# alarm_controller.net
KiCad netlist of a schematic drawn in EAGLE
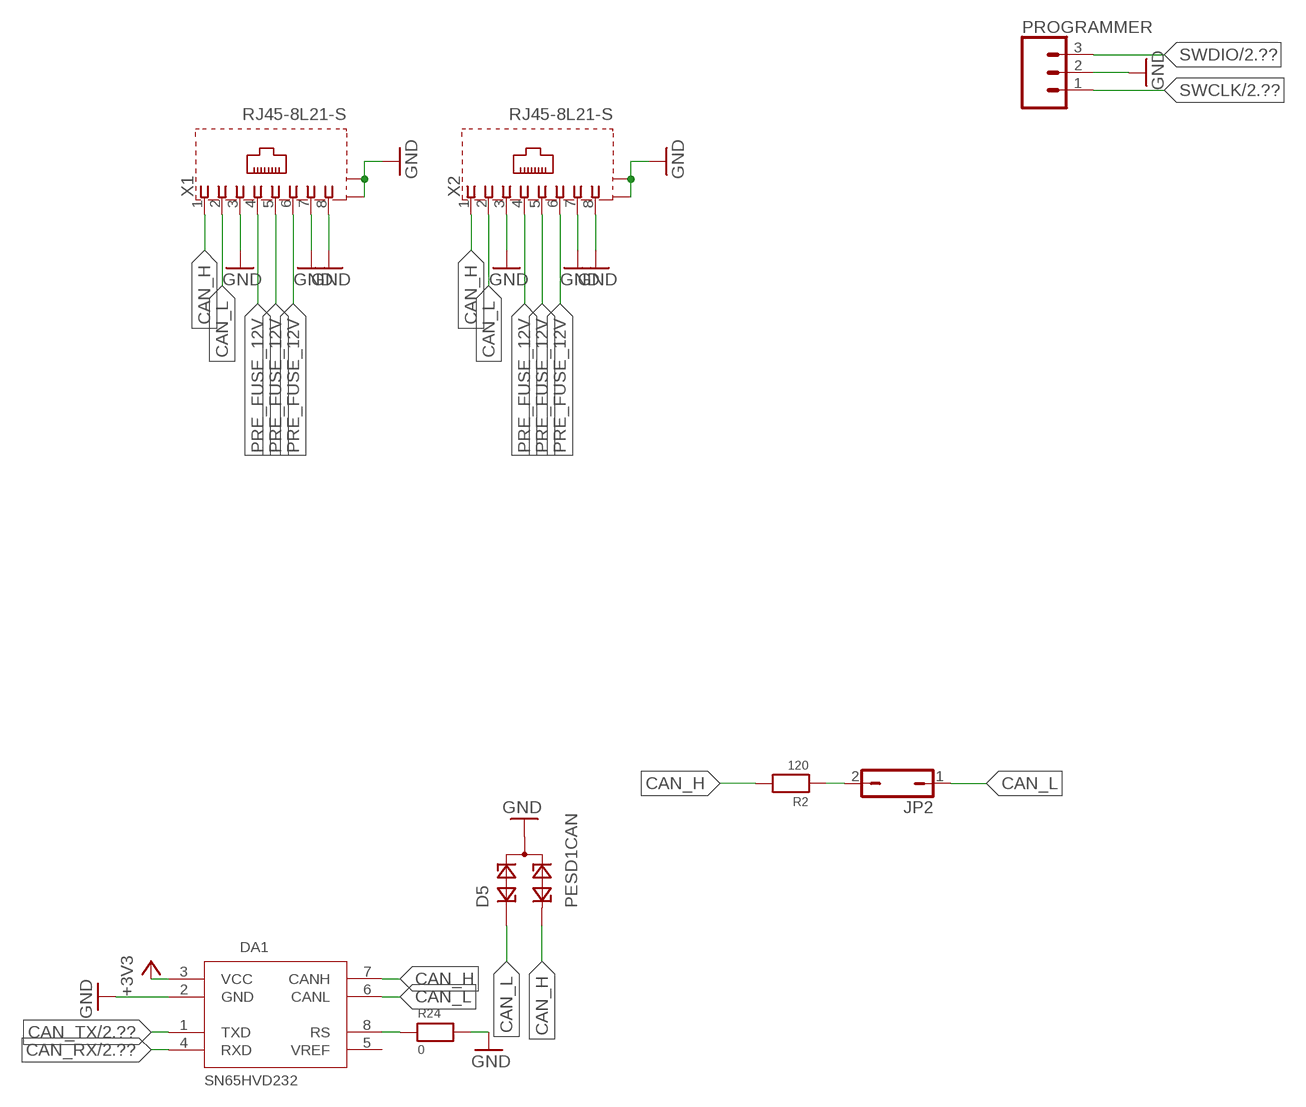
[diagram p0: schematic, sheet 1, part 1 of 2]
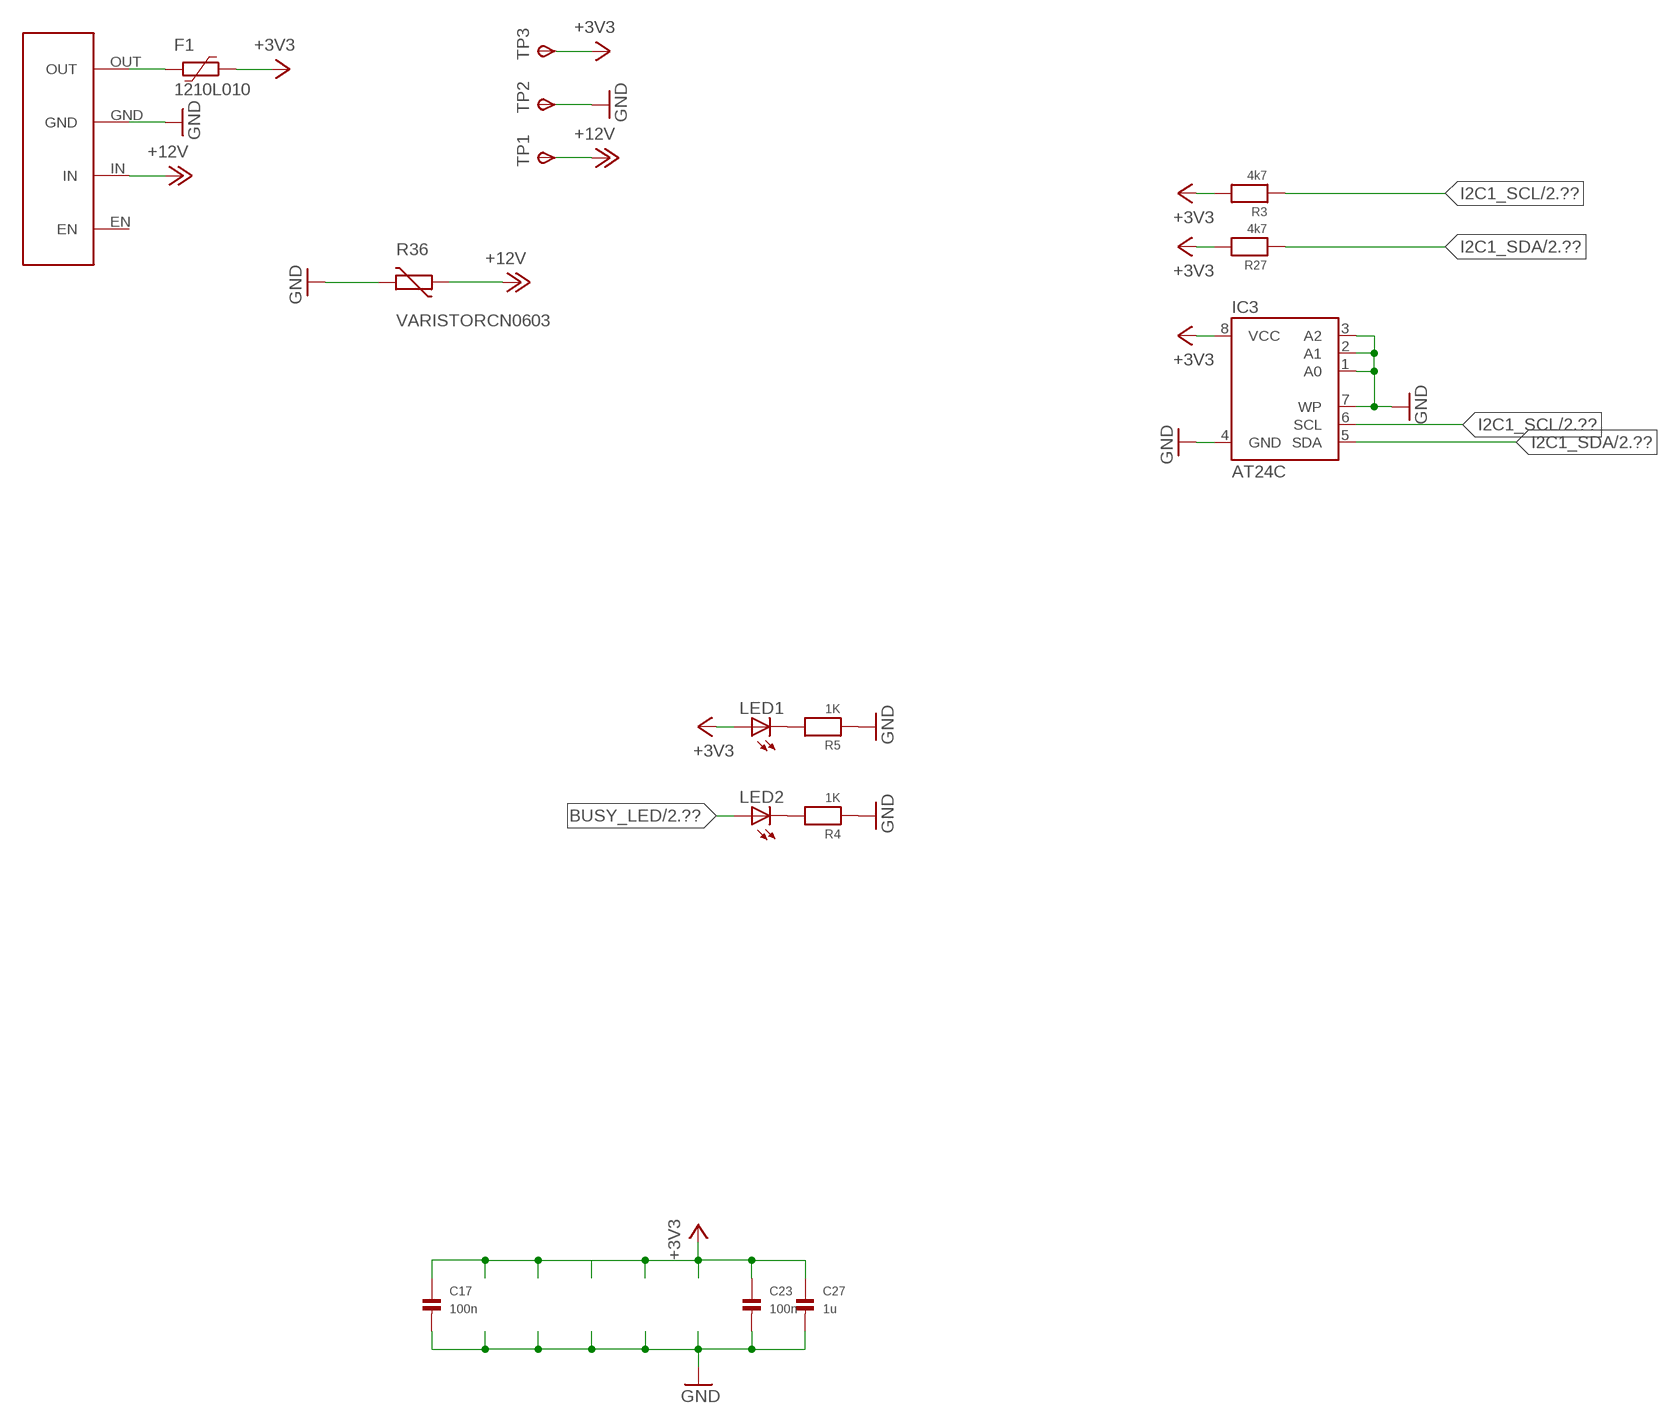
[diagram p1: schematic, sheet 1, part 2 of 2]
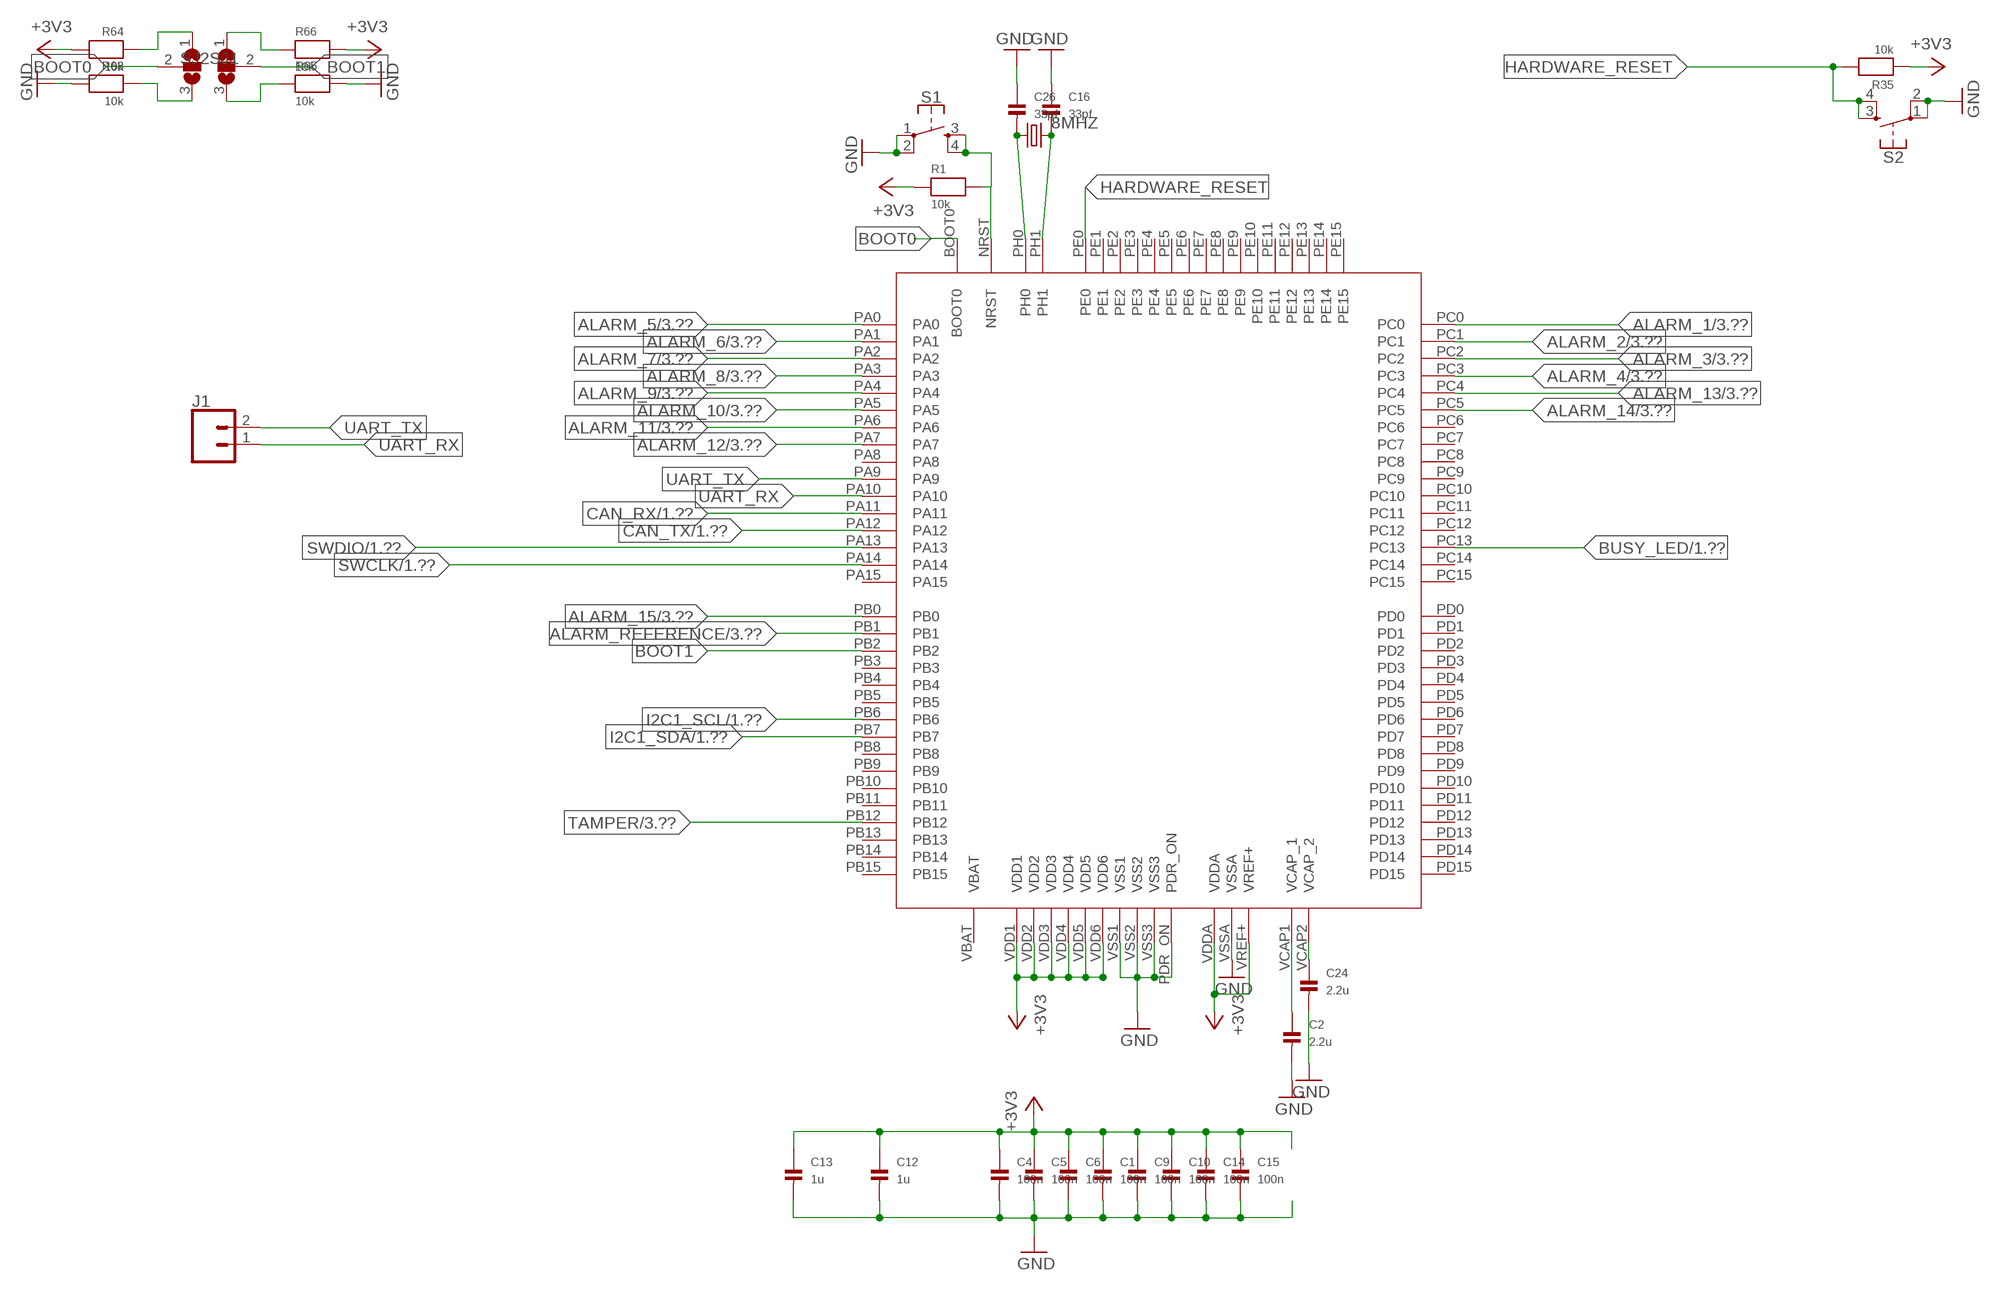
[diagram p2: schematic, sheet 2]
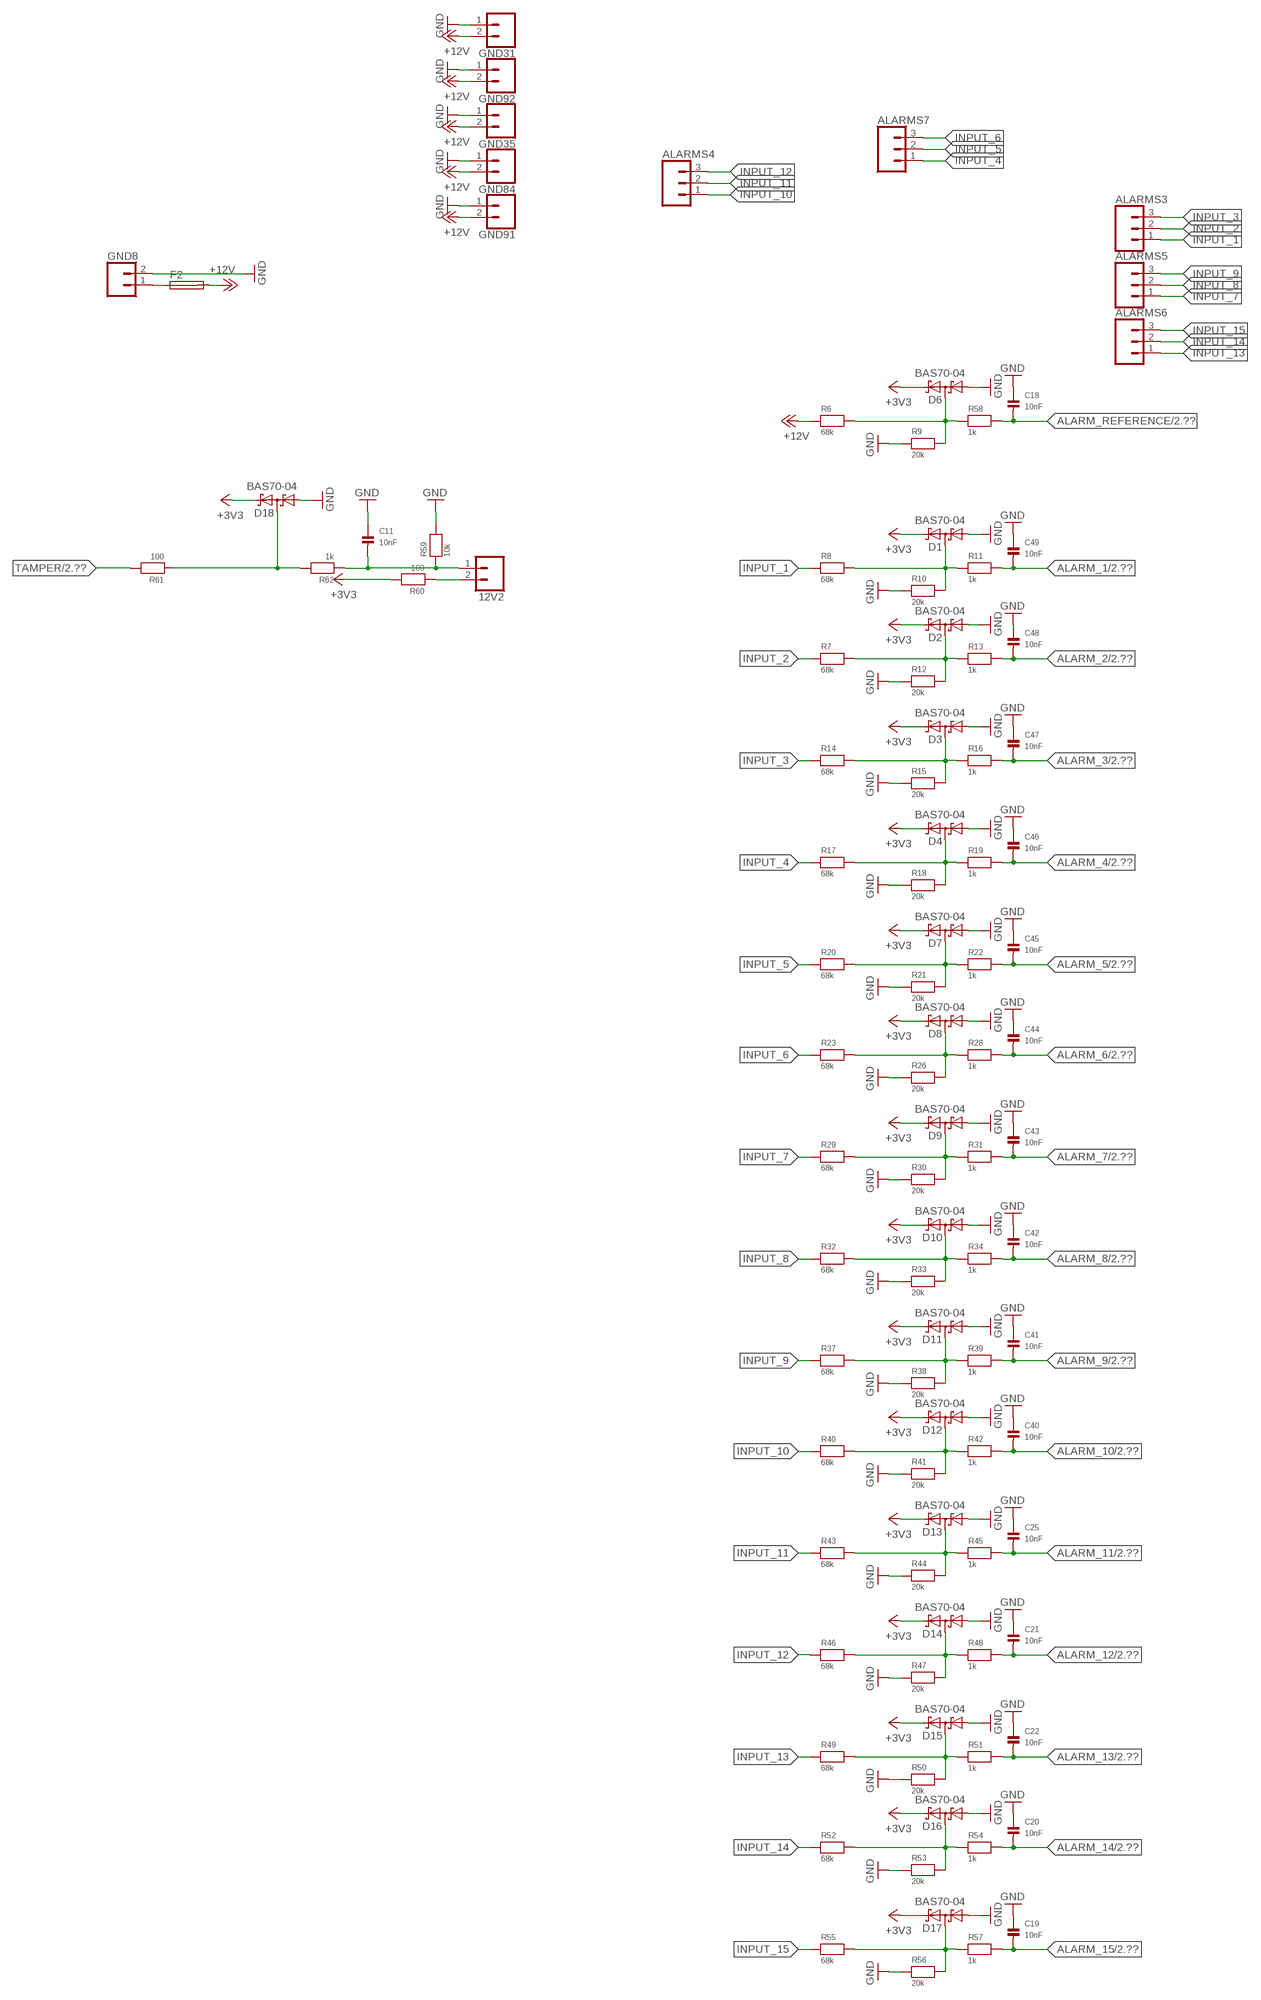
[diagram p3: schematic, sheet 3]

(export (version "E")
  (design (tool "Eeschema 10.0.6"))
  (components
    (comp (ref "8MHZ")
      (value "CRYSTALHC49UP")
      (footprint "eagle-import:HC49UP")
      (libsource (lib "eagle-import") (part "CRYSTALHC49UP"))
    )
    (comp (ref "C1")
      (value "100n")
      (footprint "eagle-import:0603")
      (libsource (lib "eagle-import") (part "CAP_CERAMIC0603"))
    )
    (comp (ref "C2")
      (value "2.2u")
      (footprint "eagle-import:0603")
      (libsource (lib "eagle-import") (part "CAP_CERAMIC0603"))
    )
    (comp (ref "C4")
      (value "100n")
      (footprint "eagle-import:0603")
      (libsource (lib "eagle-import") (part "CAP_CERAMIC0603"))
    )
    (comp (ref "C5")
      (value "100n")
      (footprint "eagle-import:0603")
      (libsource (lib "eagle-import") (part "CAP_CERAMIC0603"))
    )
    (comp (ref "C6")
      (value "100n")
      (footprint "eagle-import:0603")
      (libsource (lib "eagle-import") (part "CAP_CERAMIC0603"))
    )
    (comp (ref "C9")
      (value "100n")
      (footprint "eagle-import:0603")
      (libsource (lib "eagle-import") (part "CAP_CERAMIC0603"))
    )
    (comp (ref "C10")
      (value "100n")
      (footprint "eagle-import:0603")
      (libsource (lib "eagle-import") (part "CAP_CERAMIC0603"))
    )
    (comp (ref "C12")
      (value "1u")
      (footprint "eagle-import:0603")
      (libsource (lib "eagle-import") (part "CAP_CERAMIC0603"))
    )
    (comp (ref "C13")
      (value "1u")
      (footprint "eagle-import:0603")
      (libsource (lib "eagle-import") (part "CAP_CERAMIC0603"))
    )
    (comp (ref "C14")
      (value "100n")
      (footprint "eagle-import:0603")
      (libsource (lib "eagle-import") (part "CAP_CERAMIC0603"))
    )
    (comp (ref "C15")
      (value "100n")
      (footprint "eagle-import:0603")
      (libsource (lib "eagle-import") (part "CAP_CERAMIC0603"))
    )
    (comp (ref "C16")
      (value "33pf")
      (footprint "eagle-import:0603")
      (libsource (lib "eagle-import") (part "CAP_CERAMIC0603"))
    )
    (comp (ref "C24")
      (value "2.2u")
      (footprint "eagle-import:0603")
      (libsource (lib "eagle-import") (part "CAP_CERAMIC0603"))
    )
    (comp (ref "C26")
      (value "33pf")
      (footprint "eagle-import:0603")
      (libsource (lib "eagle-import") (part "CAP_CERAMIC0603"))
    )
    (comp (ref "J1")
      (value "CONN_02")
      (footprint "eagle-import:1X02")
      (libsource (lib "eagle-import") (part "CONN_02"))
    )
    (comp (ref "R1")
      (value "10k")
      (footprint "eagle-import:0603")
      (libsource (lib "eagle-import") (part "RESISTOR0603"))
    )
    (comp (ref "R35")
      (value "10k")
      (footprint "eagle-import:0603")
      (libsource (lib "eagle-import") (part "RESISTOR0603"))
    )
    (comp (ref "R63")
      (value "10k")
      (footprint "eagle-import:0603")
      (libsource (lib "eagle-import") (part "RESISTOR0603"))
    )
    (comp (ref "R64")
      (value "10k")
      (footprint "eagle-import:0603")
      (libsource (lib "eagle-import") (part "RESISTOR0603"))
    )
    (comp (ref "R65")
      (value "10k")
      (footprint "eagle-import:0603")
      (libsource (lib "eagle-import") (part "RESISTOR0603"))
    )
    (comp (ref "R66")
      (value "10k")
      (footprint "eagle-import:0603")
      (libsource (lib "eagle-import") (part "RESISTOR0603"))
    )
    (comp (ref "S1")
      (value "MOMENTARY-SWITCH-SPST-2-SMD-4.6X2.8MM")
      (footprint "eagle-import:TACTILE_SWITCH_SMD_4.6X2.8MM")
      (libsource (lib "eagle-import") (part "MOMENTARY-SWITCH-SPST-2-SMD-4.6X2.8MM"))
    )
    (comp (ref "S2")
      (value "MOMENTARY-SWITCH-SPST-2-SMD-4.6X2.8MM")
      (footprint "eagle-import:TACTILE_SWITCH_SMD_4.6X2.8MM")
      (libsource (lib "eagle-import") (part "MOMENTARY-SWITCH-SPST-2-SMD-4.6X2.8MM"))
    )
    (comp (ref "SJ1")
      (value "SJ2W")
      (footprint "eagle-import:SJ_2")
      (libsource (lib "eagle-import") (part "SJ2W"))
    )
    (comp (ref "SJ2")
      (value "SJ2W")
      (footprint "eagle-import:SJ_2")
      (libsource (lib "eagle-import") (part "SJ2W"))
    )
    (comp (ref "U$1")
      (value "STM32F4V_100PIN_GENERIC")
      (footprint "eagle-import:LQFP100")
      (libsource (lib "eagle-import") (part "STM32F4V_100PIN_GENERIC"))
    )
    (comp (ref "12V2")
      (value "CONN_023.5MM")
      (footprint "eagle-import:SCREWTERMINAL-3.5MM-2")
      (libsource (lib "eagle-import") (part "CONN_023.5MM"))
    )
    (comp (ref "ALARMS3")
      (value "CONN_03SCREW_LOCK")
      (footprint "eagle-import:SCREWTERMINAL-3.5MM-3_LOCK.007S")
      (libsource (lib "eagle-import") (part "CONN_03SCREW_LOCK"))
    )
    (comp (ref "ALARMS4")
      (value "CONN_03SCREW_LOCK")
      (footprint "eagle-import:SCREWTERMINAL-3.5MM-3_LOCK.007S")
      (libsource (lib "eagle-import") (part "CONN_03SCREW_LOCK"))
    )
    (comp (ref "ALARMS5")
      (value "CONN_03SCREW_LOCK")
      (footprint "eagle-import:SCREWTERMINAL-3.5MM-3_LOCK.007S")
      (libsource (lib "eagle-import") (part "CONN_03SCREW_LOCK"))
    )
    (comp (ref "ALARMS6")
      (value "CONN_03SCREW_LOCK")
      (footprint "eagle-import:SCREWTERMINAL-3.5MM-3_LOCK.007S")
      (libsource (lib "eagle-import") (part "CONN_03SCREW_LOCK"))
    )
    (comp (ref "ALARMS7")
      (value "CONN_03SCREW_LOCK")
      (footprint "eagle-import:SCREWTERMINAL-3.5MM-3_LOCK.007S")
      (libsource (lib "eagle-import") (part "CONN_03SCREW_LOCK"))
    )
    (comp (ref "C11")
      (value "10nF")
      (footprint "eagle-import:0603")
      (libsource (lib "eagle-import") (part "CAP_CERAMIC0603"))
    )
    (comp (ref "C18")
      (value "10nF")
      (footprint "eagle-import:0603")
      (libsource (lib "eagle-import") (part "CAP_CERAMIC0603"))
    )
    (comp (ref "C19")
      (value "10nF")
      (footprint "eagle-import:0603")
      (libsource (lib "eagle-import") (part "CAP_CERAMIC0603"))
    )
    (comp (ref "C20")
      (value "10nF")
      (footprint "eagle-import:0603")
      (libsource (lib "eagle-import") (part "CAP_CERAMIC0603"))
    )
    (comp (ref "C21")
      (value "10nF")
      (footprint "eagle-import:0603")
      (libsource (lib "eagle-import") (part "CAP_CERAMIC0603"))
    )
    (comp (ref "C22")
      (value "10nF")
      (footprint "eagle-import:0603")
      (libsource (lib "eagle-import") (part "CAP_CERAMIC0603"))
    )
    (comp (ref "C25")
      (value "10nF")
      (footprint "eagle-import:0603")
      (libsource (lib "eagle-import") (part "CAP_CERAMIC0603"))
    )
    (comp (ref "C40")
      (value "10nF")
      (footprint "eagle-import:0603")
      (libsource (lib "eagle-import") (part "CAP_CERAMIC0603"))
    )
    (comp (ref "C41")
      (value "10nF")
      (footprint "eagle-import:0603")
      (libsource (lib "eagle-import") (part "CAP_CERAMIC0603"))
    )
    (comp (ref "C42")
      (value "10nF")
      (footprint "eagle-import:0603")
      (libsource (lib "eagle-import") (part "CAP_CERAMIC0603"))
    )
    (comp (ref "C43")
      (value "10nF")
      (footprint "eagle-import:0603")
      (libsource (lib "eagle-import") (part "CAP_CERAMIC0603"))
    )
    (comp (ref "C44")
      (value "10nF")
      (footprint "eagle-import:0603")
      (libsource (lib "eagle-import") (part "CAP_CERAMIC0603"))
    )
    (comp (ref "C45")
      (value "10nF")
      (footprint "eagle-import:0603")
      (libsource (lib "eagle-import") (part "CAP_CERAMIC0603"))
    )
    (comp (ref "C46")
      (value "10nF")
      (footprint "eagle-import:0603")
      (libsource (lib "eagle-import") (part "CAP_CERAMIC0603"))
    )
    (comp (ref "C47")
      (value "10nF")
      (footprint "eagle-import:0603")
      (libsource (lib "eagle-import") (part "CAP_CERAMIC0603"))
    )
    (comp (ref "C48")
      (value "10nF")
      (footprint "eagle-import:0603")
      (libsource (lib "eagle-import") (part "CAP_CERAMIC0603"))
    )
    (comp (ref "C49")
      (value "10nF")
      (footprint "eagle-import:0603")
      (libsource (lib "eagle-import") (part "CAP_CERAMIC0603"))
    )
    (comp (ref "D1")
      (value "BAS70-04")
      (footprint "eagle-import:SOT23")
      (libsource (lib "eagle-import") (part "BAS70-04"))
    )
    (comp (ref "D2")
      (value "BAS70-04")
      (footprint "eagle-import:SOT23")
      (libsource (lib "eagle-import") (part "BAS70-04"))
    )
    (comp (ref "D3")
      (value "BAS70-04")
      (footprint "eagle-import:SOT23")
      (libsource (lib "eagle-import") (part "BAS70-04"))
    )
    (comp (ref "D4")
      (value "BAS70-04")
      (footprint "eagle-import:SOT23")
      (libsource (lib "eagle-import") (part "BAS70-04"))
    )
    (comp (ref "D6")
      (value "BAS70-04")
      (footprint "eagle-import:SOT23")
      (libsource (lib "eagle-import") (part "BAS70-04"))
    )
    (comp (ref "D7")
      (value "BAS70-04")
      (footprint "eagle-import:SOT23")
      (libsource (lib "eagle-import") (part "BAS70-04"))
    )
    (comp (ref "D8")
      (value "BAS70-04")
      (footprint "eagle-import:SOT23")
      (libsource (lib "eagle-import") (part "BAS70-04"))
    )
    (comp (ref "D9")
      (value "BAS70-04")
      (footprint "eagle-import:SOT23")
      (libsource (lib "eagle-import") (part "BAS70-04"))
    )
    (comp (ref "D10")
      (value "BAS70-04")
      (footprint "eagle-import:SOT23")
      (libsource (lib "eagle-import") (part "BAS70-04"))
    )
    (comp (ref "D11")
      (value "BAS70-04")
      (footprint "eagle-import:SOT23")
      (libsource (lib "eagle-import") (part "BAS70-04"))
    )
    (comp (ref "D12")
      (value "BAS70-04")
      (footprint "eagle-import:SOT23")
      (libsource (lib "eagle-import") (part "BAS70-04"))
    )
    (comp (ref "D13")
      (value "BAS70-04")
      (footprint "eagle-import:SOT23")
      (libsource (lib "eagle-import") (part "BAS70-04"))
    )
    (comp (ref "D14")
      (value "BAS70-04")
      (footprint "eagle-import:SOT23")
      (libsource (lib "eagle-import") (part "BAS70-04"))
    )
    (comp (ref "D15")
      (value "BAS70-04")
      (footprint "eagle-import:SOT23")
      (libsource (lib "eagle-import") (part "BAS70-04"))
    )
    (comp (ref "D16")
      (value "BAS70-04")
      (footprint "eagle-import:SOT23")
      (libsource (lib "eagle-import") (part "BAS70-04"))
    )
    (comp (ref "D17")
      (value "BAS70-04")
      (footprint "eagle-import:SOT23")
      (libsource (lib "eagle-import") (part "BAS70-04"))
    )
    (comp (ref "D18")
      (value "BAS70-04")
      (footprint "eagle-import:SOT23")
      (libsource (lib "eagle-import") (part "BAS70-04"))
    )
    (comp (ref "F2")
      (value "TE5")
      (footprint "eagle-import:TE5")
      (libsource (lib "eagle-import") (part "TE5"))
    )
    (comp (ref "GND8")
      (value "CONN_025MM")
      (footprint "eagle-import:SCREWTERMINAL-5MM-2")
      (libsource (lib "eagle-import") (part "CONN_025MM"))
    )
    (comp (ref "GND31")
      (value "CONN_023.5MM")
      (footprint "eagle-import:SCREWTERMINAL-3.5MM-2")
      (libsource (lib "eagle-import") (part "CONN_023.5MM"))
    )
    (comp (ref "GND35")
      (value "CONN_023.5MM")
      (footprint "eagle-import:SCREWTERMINAL-3.5MM-2")
      (libsource (lib "eagle-import") (part "CONN_023.5MM"))
    )
    (comp (ref "GND84")
      (value "CONN_023.5MM")
      (footprint "eagle-import:SCREWTERMINAL-3.5MM-2")
      (libsource (lib "eagle-import") (part "CONN_023.5MM"))
    )
    (comp (ref "GND91")
      (value "CONN_023.5MM")
      (footprint "eagle-import:SCREWTERMINAL-3.5MM-2")
      (libsource (lib "eagle-import") (part "CONN_023.5MM"))
    )
    (comp (ref "GND92")
      (value "CONN_023.5MM")
      (footprint "eagle-import:SCREWTERMINAL-3.5MM-2")
      (libsource (lib "eagle-import") (part "CONN_023.5MM"))
    )
    (comp (ref "R6")
      (value "68k")
      (footprint "eagle-import:0603")
      (libsource (lib "eagle-import") (part "RESISTOR0603"))
    )
    (comp (ref "R7")
      (value "68k")
      (footprint "eagle-import:0603")
      (libsource (lib "eagle-import") (part "RESISTOR0603"))
    )
    (comp (ref "R8")
      (value "68k")
      (footprint "eagle-import:0603")
      (libsource (lib "eagle-import") (part "RESISTOR0603"))
    )
    (comp (ref "R9")
      (value "20k")
      (footprint "eagle-import:0603")
      (libsource (lib "eagle-import") (part "RESISTOR0603"))
    )
    (comp (ref "R10")
      (value "20k")
      (footprint "eagle-import:0603")
      (libsource (lib "eagle-import") (part "RESISTOR0603"))
    )
    (comp (ref "R11")
      (value "1k")
      (footprint "eagle-import:0603")
      (libsource (lib "eagle-import") (part "RESISTOR0603"))
    )
    (comp (ref "R12")
      (value "20k")
      (footprint "eagle-import:0603")
      (libsource (lib "eagle-import") (part "RESISTOR0603"))
    )
    (comp (ref "R13")
      (value "1k")
      (footprint "eagle-import:0603")
      (libsource (lib "eagle-import") (part "RESISTOR0603"))
    )
    (comp (ref "R14")
      (value "68k")
      (footprint "eagle-import:0603")
      (libsource (lib "eagle-import") (part "RESISTOR0603"))
    )
    (comp (ref "R15")
      (value "20k")
      (footprint "eagle-import:0603")
      (libsource (lib "eagle-import") (part "RESISTOR0603"))
    )
    (comp (ref "R16")
      (value "1k")
      (footprint "eagle-import:0603")
      (libsource (lib "eagle-import") (part "RESISTOR0603"))
    )
    (comp (ref "R17")
      (value "68k")
      (footprint "eagle-import:0603")
      (libsource (lib "eagle-import") (part "RESISTOR0603"))
    )
    (comp (ref "R18")
      (value "20k")
      (footprint "eagle-import:0603")
      (libsource (lib "eagle-import") (part "RESISTOR0603"))
    )
    (comp (ref "R19")
      (value "1k")
      (footprint "eagle-import:0603")
      (libsource (lib "eagle-import") (part "RESISTOR0603"))
    )
    (comp (ref "R20")
      (value "68k")
      (footprint "eagle-import:0603")
      (libsource (lib "eagle-import") (part "RESISTOR0603"))
    )
    (comp (ref "R21")
      (value "20k")
      (footprint "eagle-import:0603")
      (libsource (lib "eagle-import") (part "RESISTOR0603"))
    )
    (comp (ref "R22")
      (value "1k")
      (footprint "eagle-import:0603")
      (libsource (lib "eagle-import") (part "RESISTOR0603"))
    )
    (comp (ref "R23")
      (value "68k")
      (footprint "eagle-import:0603")
      (libsource (lib "eagle-import") (part "RESISTOR0603"))
    )
    (comp (ref "R26")
      (value "20k")
      (footprint "eagle-import:0603")
      (libsource (lib "eagle-import") (part "RESISTOR0603"))
    )
    (comp (ref "R28")
      (value "1k")
      (footprint "eagle-import:0603")
      (libsource (lib "eagle-import") (part "RESISTOR0603"))
    )
    (comp (ref "R29")
      (value "68k")
      (footprint "eagle-import:0603")
      (libsource (lib "eagle-import") (part "RESISTOR0603"))
    )
    (comp (ref "R30")
      (value "20k")
      (footprint "eagle-import:0603")
      (libsource (lib "eagle-import") (part "RESISTOR0603"))
    )
    (comp (ref "R31")
      (value "1k")
      (footprint "eagle-import:0603")
      (libsource (lib "eagle-import") (part "RESISTOR0603"))
    )
    (comp (ref "R32")
      (value "68k")
      (footprint "eagle-import:0603")
      (libsource (lib "eagle-import") (part "RESISTOR0603"))
    )
    (comp (ref "R33")
      (value "20k")
      (footprint "eagle-import:0603")
      (libsource (lib "eagle-import") (part "RESISTOR0603"))
    )
    (comp (ref "R34")
      (value "1k")
      (footprint "eagle-import:0603")
      (libsource (lib "eagle-import") (part "RESISTOR0603"))
    )
    (comp (ref "R37")
      (value "68k")
      (footprint "eagle-import:0603")
      (libsource (lib "eagle-import") (part "RESISTOR0603"))
    )
    (comp (ref "R38")
      (value "20k")
      (footprint "eagle-import:0603")
      (libsource (lib "eagle-import") (part "RESISTOR0603"))
    )
    (comp (ref "R39")
      (value "1k")
      (footprint "eagle-import:0603")
      (libsource (lib "eagle-import") (part "RESISTOR0603"))
    )
    (comp (ref "R40")
      (value "68k")
      (footprint "eagle-import:0603")
      (libsource (lib "eagle-import") (part "RESISTOR0603"))
    )
    (comp (ref "R41")
      (value "20k")
      (footprint "eagle-import:0603")
      (libsource (lib "eagle-import") (part "RESISTOR0603"))
    )
    (comp (ref "R42")
      (value "1k")
      (footprint "eagle-import:0603")
      (libsource (lib "eagle-import") (part "RESISTOR0603"))
    )
    (comp (ref "R43")
      (value "68k")
      (footprint "eagle-import:0603")
      (libsource (lib "eagle-import") (part "RESISTOR0603"))
    )
    (comp (ref "R44")
      (value "20k")
      (footprint "eagle-import:0603")
      (libsource (lib "eagle-import") (part "RESISTOR0603"))
    )
    (comp (ref "R45")
      (value "1k")
      (footprint "eagle-import:0603")
      (libsource (lib "eagle-import") (part "RESISTOR0603"))
    )
    (comp (ref "R46")
      (value "68k")
      (footprint "eagle-import:0603")
      (libsource (lib "eagle-import") (part "RESISTOR0603"))
    )
    (comp (ref "R47")
      (value "20k")
      (footprint "eagle-import:0603")
      (libsource (lib "eagle-import") (part "RESISTOR0603"))
    )
    (comp (ref "R48")
      (value "1k")
      (footprint "eagle-import:0603")
      (libsource (lib "eagle-import") (part "RESISTOR0603"))
    )
    (comp (ref "R49")
      (value "68k")
      (footprint "eagle-import:0603")
      (libsource (lib "eagle-import") (part "RESISTOR0603"))
    )
    (comp (ref "R50")
      (value "20k")
      (footprint "eagle-import:0603")
      (libsource (lib "eagle-import") (part "RESISTOR0603"))
    )
    (comp (ref "R51")
      (value "1k")
      (footprint "eagle-import:0603")
      (libsource (lib "eagle-import") (part "RESISTOR0603"))
    )
    (comp (ref "R52")
      (value "68k")
      (footprint "eagle-import:0603")
      (libsource (lib "eagle-import") (part "RESISTOR0603"))
    )
    (comp (ref "R53")
      (value "20k")
      (footprint "eagle-import:0603")
      (libsource (lib "eagle-import") (part "RESISTOR0603"))
    )
    (comp (ref "R54")
      (value "1k")
      (footprint "eagle-import:0603")
      (libsource (lib "eagle-import") (part "RESISTOR0603"))
    )
    (comp (ref "R55")
      (value "68k")
      (footprint "eagle-import:0603")
      (libsource (lib "eagle-import") (part "RESISTOR0603"))
    )
    (comp (ref "R56")
      (value "20k")
      (footprint "eagle-import:0603")
      (libsource (lib "eagle-import") (part "RESISTOR0603"))
    )
    (comp (ref "R57")
      (value "1k")
      (footprint "eagle-import:0603")
      (libsource (lib "eagle-import") (part "RESISTOR0603"))
    )
    (comp (ref "R58")
      (value "1k")
      (footprint "eagle-import:0603")
      (libsource (lib "eagle-import") (part "RESISTOR0603"))
    )
    (comp (ref "R59")
      (value "10k")
      (footprint "eagle-import:0603")
      (libsource (lib "eagle-import") (part "RESISTOR0603"))
    )
    (comp (ref "R60")
      (value "100")
      (footprint "eagle-import:0603")
      (libsource (lib "eagle-import") (part "RESISTOR0603"))
    )
    (comp (ref "R61")
      (value "100")
      (footprint "eagle-import:0603")
      (libsource (lib "eagle-import") (part "RESISTOR0603"))
    )
    (comp (ref "R62")
      (value "1k")
      (footprint "eagle-import:0603")
      (libsource (lib "eagle-import") (part "RESISTOR0603"))
    )
    (comp (ref "C17")
      (value "100n")
      (footprint "eagle-import:0603")
      (libsource (lib "eagle-import") (part "CAP_CERAMIC0603"))
    )
    (comp (ref "C23")
      (value "100n")
      (footprint "eagle-import:0603")
      (libsource (lib "eagle-import") (part "CAP_CERAMIC0603"))
    )
    (comp (ref "C27")
      (value "1u")
      (footprint "eagle-import:0603")
      (libsource (lib "eagle-import") (part "CAP_CERAMIC0603"))
    )
    (comp (ref "D5")
      (value "PESD1CAN")
      (footprint "eagle-import:SOT23")
      (libsource (lib "eagle-import") (part "PESD1CAN"))
    )
    (comp (ref "DA1")
      (value "SN65HVD232")
      (footprint "eagle-import:SO08")
      (libsource (lib "eagle-import") (part "SN65HVD232"))
    )
    (comp (ref "F1")
      (value "1210L010")
      (footprint "eagle-import:1210L")
      (fields (field (name "MF") "Littelfuse"))
      (libsource (lib "eagle-import") (part "?1210L010"))
    )
    (comp (ref "IC3")
      (value "AT24C")
      (footprint "eagle-import:SOIC8")
      (libsource (lib "eagle-import") (part "AT24C"))
    )
    (comp (ref "JP2")
      (value "JP1Q")
      (footprint "eagle-import:JP1")
      (libsource (lib "eagle-import") (part "JP1Q"))
    )
    (comp (ref "LED1")
      (value "LEDCHIPLED_0805")
      (footprint "eagle-import:CHIPLED_0805")
      (libsource (lib "eagle-import") (part "LEDCHIPLED_0805"))
    )
    (comp (ref "LED2")
      (value "LEDCHIPLED_0805")
      (footprint "eagle-import:CHIPLED_0805")
      (libsource (lib "eagle-import") (part "LEDCHIPLED_0805"))
    )
    (comp (ref "PROGRAMMER")
      (value "CONN_03LOCK")
      (footprint "eagle-import:1X03_LOCK")
      (libsource (lib "eagle-import") (part "CONN_03LOCK"))
    )
    (comp (ref "R2")
      (value "120")
      (footprint "eagle-import:0603")
      (libsource (lib "eagle-import") (part "RESISTOR0603"))
    )
    (comp (ref "R3")
      (value "4k7")
      (footprint "eagle-import:0603")
      (libsource (lib "eagle-import") (part "RESISTOR0603"))
    )
    (comp (ref "R4")
      (value "1K")
      (footprint "eagle-import:0603")
      (libsource (lib "eagle-import") (part "RESISTOR0603"))
    )
    (comp (ref "R5")
      (value "1K")
      (footprint "eagle-import:0603")
      (libsource (lib "eagle-import") (part "RESISTOR0603"))
    )
    (comp (ref "R24")
      (value "0")
      (footprint "eagle-import:0603")
      (libsource (lib "eagle-import") (part "RESISTOR0603"))
    )
    (comp (ref "R27")
      (value "4k7")
      (footprint "eagle-import:0603")
      (libsource (lib "eagle-import") (part "RESISTOR0603"))
    )
    (comp (ref "R36")
      (value "VARISTORCN0603")
      (footprint "eagle-import:CT_CN0603")
      (libsource (lib "eagle-import") (part "VARISTORCN0603"))
    )
    (comp (ref "TP1")
      (value "TPSTP20R")
      (footprint "eagle-import:TP20R")
      (libsource (lib "eagle-import") (part "TPSTP20R"))
    )
    (comp (ref "TP2")
      (value "TPSTP20R")
      (footprint "eagle-import:TP20R")
      (libsource (lib "eagle-import") (part "TPSTP20R"))
    )
    (comp (ref "TP3")
      (value "TPSTP20R")
      (footprint "eagle-import:TP20R")
      (libsource (lib "eagle-import") (part "TPSTP20R"))
    )
    (comp (ref "U$4")
      (value "HW-613")
      (footprint "eagle-import:HW-613")
      (libsource (lib "eagle-import") (part "HW-613"))
    )
    (comp (ref "X1")
      (value "RJ45-8L21-S")
      (footprint "eagle-import:RJ45-SHIELD1")
      (libsource (lib "eagle-import") (part "RJ4521-S-8L"))
    )
    (comp (ref "X2")
      (value "RJ45-8L21-S")
      (footprint "eagle-import:RJ45-SHIELD1")
      (libsource (lib "eagle-import") (part "RJ4521-S-8L"))
    )
  )
  (nets
    (net (code "1") (name "+3V3") (class "Default")
      (node (ref "C1") (pin "1") (pinfunction "P$1_1") (pintype "passive"))
      (node (ref "C10") (pin "1") (pinfunction "P$1_1") (pintype "passive"))
      (node (ref "C12") (pin "1") (pinfunction "P$1_1") (pintype "passive"))
      (node (ref "C13") (pin "1") (pinfunction "P$1_1") (pintype "passive"))
      (node (ref "C14") (pin "1") (pinfunction "P$1_1") (pintype "passive"))
      (node (ref "C15") (pin "1") (pinfunction "P$1_1") (pintype "passive"))
      (node (ref "C17") (pin "1") (pinfunction "P$1_1") (pintype "passive"))
      (node (ref "C23") (pin "1") (pinfunction "P$1_1") (pintype "passive"))
      (node (ref "C27") (pin "1") (pinfunction "P$1_1") (pintype "passive"))
      (node (ref "C4") (pin "1") (pinfunction "P$1_1") (pintype "passive"))
      (node (ref "C5") (pin "1") (pinfunction "P$1_1") (pintype "passive"))
      (node (ref "C6") (pin "1") (pinfunction "P$1_1") (pintype "passive"))
      (node (ref "C9") (pin "1") (pinfunction "P$1_1") (pintype "passive"))
      (node (ref "D1") (pin "2") (pinfunction "C2_2") (pintype "passive"))
      (node (ref "D10") (pin "2") (pinfunction "C2_2") (pintype "passive"))
      (node (ref "D11") (pin "2") (pinfunction "C2_2") (pintype "passive"))
      (node (ref "D12") (pin "2") (pinfunction "C2_2") (pintype "passive"))
      (node (ref "D13") (pin "2") (pinfunction "C2_2") (pintype "passive"))
      (node (ref "D14") (pin "2") (pinfunction "C2_2") (pintype "passive"))
      (node (ref "D15") (pin "2") (pinfunction "C2_2") (pintype "passive"))
      (node (ref "D16") (pin "2") (pinfunction "C2_2") (pintype "passive"))
      (node (ref "D17") (pin "2") (pinfunction "C2_2") (pintype "passive"))
      (node (ref "D18") (pin "2") (pinfunction "C2_2") (pintype "passive"))
      (node (ref "D2") (pin "2") (pinfunction "C2_2") (pintype "passive"))
      (node (ref "D3") (pin "2") (pinfunction "C2_2") (pintype "passive"))
      (node (ref "D4") (pin "2") (pinfunction "C2_2") (pintype "passive"))
      (node (ref "D6") (pin "2") (pinfunction "C2_2") (pintype "passive"))
      (node (ref "D7") (pin "2") (pinfunction "C2_2") (pintype "passive"))
      (node (ref "D8") (pin "2") (pinfunction "C2_2") (pintype "passive"))
      (node (ref "D9") (pin "2") (pinfunction "C2_2") (pintype "passive"))
      (node (ref "DA1") (pin "3") (pinfunction "VCC_3") (pintype "power_in"))
      (node (ref "F1") (pin "1") (pinfunction "1_1") (pintype "passive"))
      (node (ref "IC3") (pin "8") (pinfunction "VCC_8") (pintype "power_in"))
      (node (ref "LED1") (pin "A") (pinfunction "A_A") (pintype "passive"))
      (node (ref "R1") (pin "1") (pinfunction "1_1") (pintype "passive"))
      (node (ref "R27") (pin "2") (pinfunction "2_2") (pintype "passive"))
      (node (ref "R3") (pin "2") (pinfunction "2_2") (pintype "passive"))
      (node (ref "R35") (pin "1") (pinfunction "1_1") (pintype "passive"))
      (node (ref "R60") (pin "2") (pinfunction "2_2") (pintype "passive"))
      (node (ref "R64") (pin "2") (pinfunction "2_2") (pintype "passive"))
      (node (ref "R66") (pin "2") (pinfunction "2_2") (pintype "passive"))
      (node (ref "TP3") (pin "TP") (pinfunction "PP_TP") (pintype "input"))
      (node (ref "U$1") (pin "VDD1") (pinfunction "VDD1_VDD1") (pintype "bidirectional"))
      (node (ref "U$1") (pin "VDD2") (pinfunction "VDD2_VDD2") (pintype "bidirectional"))
      (node (ref "U$1") (pin "VDD3") (pinfunction "VDD3_VDD3") (pintype "bidirectional"))
      (node (ref "U$1") (pin "VDD4") (pinfunction "VDD4_VDD4") (pintype "bidirectional"))
      (node (ref "U$1") (pin "VDD5") (pinfunction "VDD5_VDD5") (pintype "bidirectional"))
      (node (ref "U$1") (pin "VDD6") (pinfunction "VDD6_VDD6") (pintype "bidirectional"))
      (node (ref "U$1") (pin "VDDA") (pinfunction "VDDA_VDDA") (pintype "bidirectional"))
      (node (ref "U$1") (pin "VREF+") (pinfunction "VREF+_VREF+") (pintype "bidirectional"))
    )
    (net (code "2") (name "+12V") (class "Default")
      (node (ref "F2") (pin "2") (pinfunction "2_2") (pintype "passive"))
      (node (ref "GND31") (pin "2") (pinfunction "2_2") (pintype "passive"))
      (node (ref "GND35") (pin "2") (pinfunction "2_2") (pintype "passive"))
      (node (ref "GND84") (pin "2") (pinfunction "2_2") (pintype "passive"))
      (node (ref "GND91") (pin "2") (pinfunction "2_2") (pintype "passive"))
      (node (ref "GND92") (pin "2") (pinfunction "2_2") (pintype "passive"))
      (node (ref "R36") (pin "1") (pinfunction "1_1") (pintype "passive"))
      (node (ref "R6") (pin "1") (pinfunction "1_1") (pintype "passive"))
      (node (ref "TP1") (pin "TP") (pinfunction "PP_TP") (pintype "input"))
      (node (ref "U$4") (pin "IN") (pinfunction "IN_IN") (pintype "bidirectional"))
    )
    (net (code "3") (name "ALARM_1") (class "Default")
      (node (ref "C49") (pin "2") (pinfunction "P$2_2") (pintype "passive"))
      (node (ref "R11") (pin "2") (pinfunction "2_2") (pintype "passive"))
      (node (ref "U$1") (pin "PC0") (pinfunction "PC0_PC0") (pintype "bidirectional"))
    )
    (net (code "4") (name "ALARM_2") (class "Default")
      (node (ref "C48") (pin "2") (pinfunction "P$2_2") (pintype "passive"))
      (node (ref "R13") (pin "2") (pinfunction "2_2") (pintype "passive"))
      (node (ref "U$1") (pin "PC1") (pinfunction "PC1_PC1") (pintype "bidirectional"))
    )
    (net (code "5") (name "ALARM_3") (class "Default")
      (node (ref "C47") (pin "2") (pinfunction "P$2_2") (pintype "passive"))
      (node (ref "R16") (pin "2") (pinfunction "2_2") (pintype "passive"))
      (node (ref "U$1") (pin "PC2") (pinfunction "PC2_PC2") (pintype "bidirectional"))
    )
    (net (code "6") (name "ALARM_4") (class "Default")
      (node (ref "C46") (pin "2") (pinfunction "P$2_2") (pintype "passive"))
      (node (ref "R19") (pin "2") (pinfunction "2_2") (pintype "passive"))
      (node (ref "U$1") (pin "PC3") (pinfunction "PC3_PC3") (pintype "bidirectional"))
    )
    (net (code "7") (name "ALARM_5") (class "Default")
      (node (ref "C45") (pin "2") (pinfunction "P$2_2") (pintype "passive"))
      (node (ref "R22") (pin "2") (pinfunction "2_2") (pintype "passive"))
      (node (ref "U$1") (pin "PA0") (pinfunction "PA0_PA0") (pintype "bidirectional"))
    )
    (net (code "8") (name "ALARM_6") (class "Default")
      (node (ref "C44") (pin "2") (pinfunction "P$2_2") (pintype "passive"))
      (node (ref "R28") (pin "2") (pinfunction "2_2") (pintype "passive"))
      (node (ref "U$1") (pin "PA1") (pinfunction "PA1_PA1") (pintype "bidirectional"))
    )
    (net (code "9") (name "ALARM_7") (class "Default")
      (node (ref "C43") (pin "2") (pinfunction "P$2_2") (pintype "passive"))
      (node (ref "R31") (pin "2") (pinfunction "2_2") (pintype "passive"))
      (node (ref "U$1") (pin "PA2") (pinfunction "PA2_PA2") (pintype "bidirectional"))
    )
    (net (code "10") (name "ALARM_8") (class "Default")
      (node (ref "C42") (pin "2") (pinfunction "P$2_2") (pintype "passive"))
      (node (ref "R34") (pin "2") (pinfunction "2_2") (pintype "passive"))
      (node (ref "U$1") (pin "PA3") (pinfunction "PA3_PA3") (pintype "bidirectional"))
    )
    (net (code "11") (name "ALARM_9") (class "Default")
      (node (ref "C41") (pin "2") (pinfunction "P$2_2") (pintype "passive"))
      (node (ref "R39") (pin "2") (pinfunction "2_2") (pintype "passive"))
      (node (ref "U$1") (pin "PA4") (pinfunction "PA4_PA4") (pintype "bidirectional"))
    )
    (net (code "12") (name "ALARM_10") (class "Default")
      (node (ref "C40") (pin "2") (pinfunction "P$2_2") (pintype "passive"))
      (node (ref "R42") (pin "2") (pinfunction "2_2") (pintype "passive"))
      (node (ref "U$1") (pin "PA5") (pinfunction "PA5_PA5") (pintype "bidirectional"))
    )
    (net (code "13") (name "ALARM_11") (class "Default")
      (node (ref "C25") (pin "2") (pinfunction "P$2_2") (pintype "passive"))
      (node (ref "R45") (pin "2") (pinfunction "2_2") (pintype "passive"))
      (node (ref "U$1") (pin "PA6") (pinfunction "PA6_PA6") (pintype "bidirectional"))
    )
    (net (code "14") (name "ALARM_12") (class "Default")
      (node (ref "C21") (pin "2") (pinfunction "P$2_2") (pintype "passive"))
      (node (ref "R48") (pin "2") (pinfunction "2_2") (pintype "passive"))
      (node (ref "U$1") (pin "PA7") (pinfunction "PA7_PA7") (pintype "bidirectional"))
    )
    (net (code "15") (name "ALARM_13") (class "Default")
      (node (ref "C22") (pin "2") (pinfunction "P$2_2") (pintype "passive"))
      (node (ref "R51") (pin "2") (pinfunction "2_2") (pintype "passive"))
      (node (ref "U$1") (pin "PC4") (pinfunction "PC4_PC4") (pintype "bidirectional"))
    )
    (net (code "16") (name "ALARM_14") (class "Default")
      (node (ref "C20") (pin "2") (pinfunction "P$2_2") (pintype "passive"))
      (node (ref "R54") (pin "2") (pinfunction "2_2") (pintype "passive"))
      (node (ref "U$1") (pin "PC5") (pinfunction "PC5_PC5") (pintype "bidirectional"))
    )
    (net (code "17") (name "ALARM_15") (class "Default")
      (node (ref "C19") (pin "2") (pinfunction "P$2_2") (pintype "passive"))
      (node (ref "R57") (pin "2") (pinfunction "2_2") (pintype "passive"))
      (node (ref "U$1") (pin "PB0") (pinfunction "PB0_PB0") (pintype "bidirectional"))
    )
    (net (code "18") (name "ALARM_REFERENCE") (class "Default")
      (node (ref "C18") (pin "2") (pinfunction "P$2_2") (pintype "passive"))
      (node (ref "R58") (pin "2") (pinfunction "2_2") (pintype "passive"))
      (node (ref "U$1") (pin "PB1") (pinfunction "PB1_PB1") (pintype "bidirectional"))
    )
    (net (code "19") (name "BOOT0") (class "Default")
      (node (ref "SJ1") (pin "2") (pinfunction "2_2") (pintype "passive"))
      (node (ref "U$1") (pin "BOOT0") (pinfunction "BOOT0_BOOT0") (pintype "bidirectional"))
    )
    (net (code "20") (name "BOOT1") (class "Default")
      (node (ref "SJ2") (pin "2") (pinfunction "2_2") (pintype "passive"))
      (node (ref "U$1") (pin "PB2") (pinfunction "PB2_PB2") (pintype "bidirectional"))
    )
    (net (code "21") (name "BUSY_LED") (class "Default")
      (node (ref "LED2") (pin "A") (pinfunction "A_A") (pintype "passive"))
      (node (ref "U$1") (pin "PC13") (pinfunction "PC13_PC13") (pintype "bidirectional"))
    )
    (net (code "22") (name "CAN_H") (class "Default")
      (node (ref "D5") (pin "2") (pinfunction "2_2") (pintype "passive"))
      (node (ref "DA1") (pin "7") (pinfunction "CANH_7") (pintype "bidirectional"))
      (node (ref "R2") (pin "2") (pinfunction "2_2") (pintype "passive"))
      (node (ref "X1") (pin "1") (pinfunction "1_1") (pintype "passive"))
      (node (ref "X2") (pin "1") (pinfunction "1_1") (pintype "passive"))
    )
    (net (code "23") (name "CAN_L") (class "Default")
      (node (ref "D5") (pin "1") (pinfunction "1_1") (pintype "passive"))
      (node (ref "DA1") (pin "6") (pinfunction "CANL_6") (pintype "bidirectional"))
      (node (ref "JP2") (pin "1") (pinfunction "1_1") (pintype "passive"))
      (node (ref "X1") (pin "2") (pinfunction "2_2") (pintype "passive"))
      (node (ref "X2") (pin "2") (pinfunction "2_2") (pintype "passive"))
    )
    (net (code "24") (name "CAN_RX") (class "Default")
      (node (ref "DA1") (pin "4") (pinfunction "RXD_4") (pintype "output"))
      (node (ref "U$1") (pin "PA11") (pinfunction "PA11_PA11") (pintype "bidirectional"))
    )
    (net (code "25") (name "CAN_TX") (class "Default")
      (node (ref "DA1") (pin "1") (pinfunction "TXD_1") (pintype "input"))
      (node (ref "U$1") (pin "PA12") (pinfunction "PA12_PA12") (pintype "bidirectional"))
    )
    (net (code "26") (name "GND") (class "Default")
      (node (ref "C1") (pin "2") (pinfunction "P$2_2") (pintype "passive"))
      (node (ref "C10") (pin "2") (pinfunction "P$2_2") (pintype "passive"))
      (node (ref "C11") (pin "1") (pinfunction "P$1_1") (pintype "passive"))
      (node (ref "C12") (pin "2") (pinfunction "P$2_2") (pintype "passive"))
      (node (ref "C13") (pin "2") (pinfunction "P$2_2") (pintype "passive"))
      (node (ref "C14") (pin "2") (pinfunction "P$2_2") (pintype "passive"))
      (node (ref "C15") (pin "2") (pinfunction "P$2_2") (pintype "passive"))
      (node (ref "C16") (pin "1") (pinfunction "P$1_1") (pintype "passive"))
      (node (ref "C17") (pin "2") (pinfunction "P$2_2") (pintype "passive"))
      (node (ref "C18") (pin "1") (pinfunction "P$1_1") (pintype "passive"))
      (node (ref "C19") (pin "1") (pinfunction "P$1_1") (pintype "passive"))
      (node (ref "C2") (pin "2") (pinfunction "P$2_2") (pintype "passive"))
      (node (ref "C20") (pin "1") (pinfunction "P$1_1") (pintype "passive"))
      (node (ref "C21") (pin "1") (pinfunction "P$1_1") (pintype "passive"))
      (node (ref "C22") (pin "1") (pinfunction "P$1_1") (pintype "passive"))
      (node (ref "C23") (pin "2") (pinfunction "P$2_2") (pintype "passive"))
      (node (ref "C24") (pin "2") (pinfunction "P$2_2") (pintype "passive"))
      (node (ref "C25") (pin "1") (pinfunction "P$1_1") (pintype "passive"))
      (node (ref "C26") (pin "1") (pinfunction "P$1_1") (pintype "passive"))
      (node (ref "C27") (pin "2") (pinfunction "P$2_2") (pintype "passive"))
      (node (ref "C4") (pin "2") (pinfunction "P$2_2") (pintype "passive"))
      (node (ref "C40") (pin "1") (pinfunction "P$1_1") (pintype "passive"))
      (node (ref "C41") (pin "1") (pinfunction "P$1_1") (pintype "passive"))
      (node (ref "C42") (pin "1") (pinfunction "P$1_1") (pintype "passive"))
      (node (ref "C43") (pin "1") (pinfunction "P$1_1") (pintype "passive"))
      (node (ref "C44") (pin "1") (pinfunction "P$1_1") (pintype "passive"))
      (node (ref "C45") (pin "1") (pinfunction "P$1_1") (pintype "passive"))
      (node (ref "C46") (pin "1") (pinfunction "P$1_1") (pintype "passive"))
      (node (ref "C47") (pin "1") (pinfunction "P$1_1") (pintype "passive"))
      (node (ref "C48") (pin "1") (pinfunction "P$1_1") (pintype "passive"))
      (node (ref "C49") (pin "1") (pinfunction "P$1_1") (pintype "passive"))
      (node (ref "C5") (pin "2") (pinfunction "P$2_2") (pintype "passive"))
      (node (ref "C6") (pin "2") (pinfunction "P$2_2") (pintype "passive"))
      (node (ref "C9") (pin "2") (pinfunction "P$2_2") (pintype "passive"))
      (node (ref "D1") (pin "1") (pinfunction "A1_1") (pintype "passive"))
      (node (ref "D10") (pin "1") (pinfunction "A1_1") (pintype "passive"))
      (node (ref "D11") (pin "1") (pinfunction "A1_1") (pintype "passive"))
      (node (ref "D12") (pin "1") (pinfunction "A1_1") (pintype "passive"))
      (node (ref "D13") (pin "1") (pinfunction "A1_1") (pintype "passive"))
      (node (ref "D14") (pin "1") (pinfunction "A1_1") (pintype "passive"))
      (node (ref "D15") (pin "1") (pinfunction "A1_1") (pintype "passive"))
      (node (ref "D16") (pin "1") (pinfunction "A1_1") (pintype "passive"))
      (node (ref "D17") (pin "1") (pinfunction "A1_1") (pintype "passive"))
      (node (ref "D18") (pin "1") (pinfunction "A1_1") (pintype "passive"))
      (node (ref "D2") (pin "1") (pinfunction "A1_1") (pintype "passive"))
      (node (ref "D3") (pin "1") (pinfunction "A1_1") (pintype "passive"))
      (node (ref "D4") (pin "1") (pinfunction "A1_1") (pintype "passive"))
      (node (ref "D5") (pin "3") (pinfunction "3_3") (pintype "passive"))
      (node (ref "D6") (pin "1") (pinfunction "A1_1") (pintype "passive"))
      (node (ref "D7") (pin "1") (pinfunction "A1_1") (pintype "passive"))
      (node (ref "D8") (pin "1") (pinfunction "A1_1") (pintype "passive"))
      (node (ref "D9") (pin "1") (pinfunction "A1_1") (pintype "passive"))
      (node (ref "DA1") (pin "2") (pinfunction "GND_2") (pintype "power_in"))
      (node (ref "GND31") (pin "1") (pinfunction "1_1") (pintype "passive"))
      (node (ref "GND35") (pin "1") (pinfunction "1_1") (pintype "passive"))
      (node (ref "GND8") (pin "2") (pinfunction "2_2") (pintype "passive"))
      (node (ref "GND84") (pin "1") (pinfunction "1_1") (pintype "passive"))
      (node (ref "GND91") (pin "1") (pinfunction "1_1") (pintype "passive"))
      (node (ref "GND92") (pin "1") (pinfunction "1_1") (pintype "passive"))
      (node (ref "IC3") (pin "1") (pinfunction "A0_1") (pintype "input"))
      (node (ref "IC3") (pin "2") (pinfunction "A1_2") (pintype "input"))
      (node (ref "IC3") (pin "3") (pinfunction "A2_3") (pintype "input"))
      (node (ref "IC3") (pin "4") (pinfunction "GND_4") (pintype "power_in"))
      (node (ref "IC3") (pin "7") (pinfunction "WP_7") (pintype "input"))
      (node (ref "PROGRAMMER") (pin "2") (pinfunction "2_2") (pintype "passive"))
      (node (ref "R10") (pin "1") (pinfunction "1_1") (pintype "passive"))
      (node (ref "R12") (pin "1") (pinfunction "1_1") (pintype "passive"))
      (node (ref "R15") (pin "1") (pinfunction "1_1") (pintype "passive"))
      (node (ref "R18") (pin "1") (pinfunction "1_1") (pintype "passive"))
      (node (ref "R21") (pin "1") (pinfunction "1_1") (pintype "passive"))
      (node (ref "R24") (pin "2") (pinfunction "2_2") (pintype "passive"))
      (node (ref "R26") (pin "1") (pinfunction "1_1") (pintype "passive"))
      (node (ref "R30") (pin "1") (pinfunction "1_1") (pintype "passive"))
      (node (ref "R33") (pin "1") (pinfunction "1_1") (pintype "passive"))
      (node (ref "R36") (pin "2") (pinfunction "2_2") (pintype "passive"))
      (node (ref "R38") (pin "1") (pinfunction "1_1") (pintype "passive"))
      (node (ref "R4") (pin "1") (pinfunction "1_1") (pintype "passive"))
      (node (ref "R41") (pin "1") (pinfunction "1_1") (pintype "passive"))
      (node (ref "R44") (pin "1") (pinfunction "1_1") (pintype "passive"))
      (node (ref "R47") (pin "1") (pinfunction "1_1") (pintype "passive"))
      (node (ref "R5") (pin "1") (pinfunction "1_1") (pintype "passive"))
      (node (ref "R50") (pin "1") (pinfunction "1_1") (pintype "passive"))
      (node (ref "R53") (pin "1") (pinfunction "1_1") (pintype "passive"))
      (node (ref "R56") (pin "1") (pinfunction "1_1") (pintype "passive"))
      (node (ref "R59") (pin "2") (pinfunction "2_2") (pintype "passive"))
      (node (ref "R63") (pin "2") (pinfunction "2_2") (pintype "passive"))
      (node (ref "R65") (pin "2") (pinfunction "2_2") (pintype "passive"))
      (node (ref "R9") (pin "1") (pinfunction "1_1") (pintype "passive"))
      (node (ref "S1") (pin "1") (pinfunction "1_1") (pintype "passive"))
      (node (ref "S1") (pin "2") (pinfunction "2_2") (pintype "passive"))
      (node (ref "S2") (pin "1") (pinfunction "1_1") (pintype "passive"))
      (node (ref "S2") (pin "2") (pinfunction "2_2") (pintype "passive"))
      (node (ref "TP2") (pin "TP") (pinfunction "PP_TP") (pintype "input"))
      (node (ref "U$1") (pin "PDR_ON") (pinfunction "PDR_ON_PDR_ON") (pintype "bidirectional"))
      (node (ref "U$1") (pin "VSS1") (pinfunction "VSS1_VSS1") (pintype "bidirectional"))
      (node (ref "U$1") (pin "VSS2") (pinfunction "VSS2_VSS2") (pintype "bidirectional"))
      (node (ref "U$1") (pin "VSS3") (pinfunction "VSS3_VSS3") (pintype "bidirectional"))
      (node (ref "U$1") (pin "VSSA") (pinfunction "VSSA_VSSA") (pintype "bidirectional"))
      (node (ref "U$4") (pin "GND") (pinfunction "GND_GND") (pintype "bidirectional"))
      (node (ref "X1") (pin "3") (pinfunction "3_3") (pintype "passive"))
      (node (ref "X1") (pin "7") (pinfunction "7_7") (pintype "passive"))
      (node (ref "X1") (pin "8") (pinfunction "8_8") (pintype "passive"))
      (node (ref "X1") (pin "S1") (pinfunction "S_S1") (pintype "passive"))
      (node (ref "X1") (pin "S2") (pinfunction "S_S2") (pintype "passive"))
      (node (ref "X2") (pin "3") (pinfunction "3_3") (pintype "passive"))
      (node (ref "X2") (pin "7") (pinfunction "7_7") (pintype "passive"))
      (node (ref "X2") (pin "8") (pinfunction "8_8") (pintype "passive"))
      (node (ref "X2") (pin "S1") (pinfunction "S_S1") (pintype "passive"))
      (node (ref "X2") (pin "S2") (pinfunction "S_S2") (pintype "passive"))
    )
    (net (code "27") (name "HARDWARE_RESET") (class "Default")
      (node (ref "R35") (pin "2") (pinfunction "2_2") (pintype "passive"))
      (node (ref "S2") (pin "3") (pinfunction "3_3") (pintype "passive"))
      (node (ref "S2") (pin "4") (pinfunction "4_4") (pintype "passive"))
      (node (ref "U$1") (pin "PE0") (pinfunction "PE0_PE0") (pintype "bidirectional"))
    )
    (net (code "28") (name "I2C1_SCL") (class "Default")
      (node (ref "IC3") (pin "6") (pinfunction "SCL_6") (pintype "bidirectional"))
      (node (ref "R3") (pin "1") (pinfunction "1_1") (pintype "passive"))
      (node (ref "U$1") (pin "PB6") (pinfunction "PB6_PB6") (pintype "bidirectional"))
    )
    (net (code "29") (name "I2C1_SDA") (class "Default")
      (node (ref "IC3") (pin "5") (pinfunction "SDA_5") (pintype "bidirectional"))
      (node (ref "R27") (pin "1") (pinfunction "1_1") (pintype "passive"))
      (node (ref "U$1") (pin "PB7") (pinfunction "PB7_PB7") (pintype "bidirectional"))
    )
    (net (code "30") (name "INPUT_1") (class "Default")
      (node (ref "ALARMS3") (pin "1") (pinfunction "1_1") (pintype "passive"))
      (node (ref "R8") (pin "1") (pinfunction "1_1") (pintype "passive"))
    )
    (net (code "31") (name "INPUT_2") (class "Default")
      (node (ref "ALARMS3") (pin "2") (pinfunction "2_2") (pintype "passive"))
      (node (ref "R7") (pin "1") (pinfunction "1_1") (pintype "passive"))
    )
    (net (code "32") (name "INPUT_3") (class "Default")
      (node (ref "ALARMS3") (pin "3") (pinfunction "3_3") (pintype "passive"))
      (node (ref "R14") (pin "1") (pinfunction "1_1") (pintype "passive"))
    )
    (net (code "33") (name "INPUT_4") (class "Default")
      (node (ref "ALARMS7") (pin "1") (pinfunction "1_1") (pintype "passive"))
      (node (ref "R17") (pin "1") (pinfunction "1_1") (pintype "passive"))
    )
    (net (code "34") (name "INPUT_5") (class "Default")
      (node (ref "ALARMS7") (pin "2") (pinfunction "2_2") (pintype "passive"))
      (node (ref "R20") (pin "1") (pinfunction "1_1") (pintype "passive"))
    )
    (net (code "35") (name "INPUT_6") (class "Default")
      (node (ref "ALARMS7") (pin "3") (pinfunction "3_3") (pintype "passive"))
      (node (ref "R23") (pin "1") (pinfunction "1_1") (pintype "passive"))
    )
    (net (code "36") (name "INPUT_7") (class "Default")
      (node (ref "ALARMS5") (pin "1") (pinfunction "1_1") (pintype "passive"))
      (node (ref "R29") (pin "1") (pinfunction "1_1") (pintype "passive"))
    )
    (net (code "37") (name "INPUT_8") (class "Default")
      (node (ref "ALARMS5") (pin "2") (pinfunction "2_2") (pintype "passive"))
      (node (ref "R32") (pin "1") (pinfunction "1_1") (pintype "passive"))
    )
    (net (code "38") (name "INPUT_9") (class "Default")
      (node (ref "ALARMS5") (pin "3") (pinfunction "3_3") (pintype "passive"))
      (node (ref "R37") (pin "1") (pinfunction "1_1") (pintype "passive"))
    )
    (net (code "39") (name "INPUT_10") (class "Default")
      (node (ref "ALARMS4") (pin "1") (pinfunction "1_1") (pintype "passive"))
      (node (ref "R40") (pin "1") (pinfunction "1_1") (pintype "passive"))
    )
    (net (code "40") (name "INPUT_11") (class "Default")
      (node (ref "ALARMS4") (pin "2") (pinfunction "2_2") (pintype "passive"))
      (node (ref "R43") (pin "1") (pinfunction "1_1") (pintype "passive"))
    )
    (net (code "41") (name "INPUT_12") (class "Default")
      (node (ref "ALARMS4") (pin "3") (pinfunction "3_3") (pintype "passive"))
      (node (ref "R46") (pin "1") (pinfunction "1_1") (pintype "passive"))
    )
    (net (code "42") (name "INPUT_13") (class "Default")
      (node (ref "ALARMS6") (pin "1") (pinfunction "1_1") (pintype "passive"))
      (node (ref "R49") (pin "1") (pinfunction "1_1") (pintype "passive"))
    )
    (net (code "43") (name "INPUT_14") (class "Default")
      (node (ref "ALARMS6") (pin "2") (pinfunction "2_2") (pintype "passive"))
      (node (ref "R52") (pin "1") (pinfunction "1_1") (pintype "passive"))
    )
    (net (code "44") (name "INPUT_15") (class "Default")
      (node (ref "ALARMS6") (pin "3") (pinfunction "3_3") (pintype "passive"))
      (node (ref "R55") (pin "1") (pinfunction "1_1") (pintype "passive"))
    )
    (net (code "45") (name "Net-(12V2-Pad2)") (class "Default")
      (node (ref "12V2") (pin "2") (pinfunction "2_2") (pintype "passive"))
      (node (ref "R60") (pin "1") (pinfunction "1_1") (pintype "passive"))
    )
    (net (code "46") (name "Net-(C2-P$1)") (class "Default")
      (node (ref "C2") (pin "1") (pinfunction "P$1_1") (pintype "passive"))
      (node (ref "U$1") (pin "VCAP1") (pinfunction "VCAP_1_VCAP1") (pintype "bidirectional"))
    )
    (net (code "47") (name "Net-(C11-P$2)") (class "Default")
      (node (ref "12V2") (pin "1") (pinfunction "1_1") (pintype "passive"))
      (node (ref "C11") (pin "2") (pinfunction "P$2_2") (pintype "passive"))
      (node (ref "R59") (pin "1") (pinfunction "1_1") (pintype "passive"))
      (node (ref "R62") (pin "1") (pinfunction "1_1") (pintype "passive"))
    )
    (net (code "48") (name "Net-(C16-P$2)") (class "Default")
      (node (ref "8MHZ") (pin "2") (pinfunction "2_2") (pintype "passive"))
      (node (ref "C16") (pin "2") (pinfunction "P$2_2") (pintype "passive"))
      (node (ref "U$1") (pin "PH1") (pinfunction "PH1_PH1") (pintype "bidirectional"))
    )
    (net (code "49") (name "Net-(C24-P$1)") (class "Default")
      (node (ref "C24") (pin "1") (pinfunction "P$1_1") (pintype "passive"))
      (node (ref "U$1") (pin "VCAP2") (pinfunction "VCAP_2_VCAP2") (pintype "bidirectional"))
    )
    (net (code "50") (name "Net-(C26-P$2)") (class "Default")
      (node (ref "8MHZ") (pin "1") (pinfunction "1_1") (pintype "passive"))
      (node (ref "C26") (pin "2") (pinfunction "P$2_2") (pintype "passive"))
      (node (ref "U$1") (pin "PH0") (pinfunction "PH0_PH0") (pintype "bidirectional"))
    )
    (net (code "51") (name "Net-(D1-C1A2)") (class "Default")
      (node (ref "D1") (pin "3") (pinfunction "C1A2_3") (pintype "passive"))
      (node (ref "R10") (pin "2") (pinfunction "2_2") (pintype "passive"))
      (node (ref "R11") (pin "1") (pinfunction "1_1") (pintype "passive"))
      (node (ref "R8") (pin "2") (pinfunction "2_2") (pintype "passive"))
    )
    (net (code "52") (name "Net-(D2-C1A2)") (class "Default")
      (node (ref "D2") (pin "3") (pinfunction "C1A2_3") (pintype "passive"))
      (node (ref "R12") (pin "2") (pinfunction "2_2") (pintype "passive"))
      (node (ref "R13") (pin "1") (pinfunction "1_1") (pintype "passive"))
      (node (ref "R7") (pin "2") (pinfunction "2_2") (pintype "passive"))
    )
    (net (code "53") (name "Net-(D3-C1A2)") (class "Default")
      (node (ref "D3") (pin "3") (pinfunction "C1A2_3") (pintype "passive"))
      (node (ref "R14") (pin "2") (pinfunction "2_2") (pintype "passive"))
      (node (ref "R15") (pin "2") (pinfunction "2_2") (pintype "passive"))
      (node (ref "R16") (pin "1") (pinfunction "1_1") (pintype "passive"))
    )
    (net (code "54") (name "Net-(D4-C1A2)") (class "Default")
      (node (ref "D4") (pin "3") (pinfunction "C1A2_3") (pintype "passive"))
      (node (ref "R17") (pin "2") (pinfunction "2_2") (pintype "passive"))
      (node (ref "R18") (pin "2") (pinfunction "2_2") (pintype "passive"))
      (node (ref "R19") (pin "1") (pinfunction "1_1") (pintype "passive"))
    )
    (net (code "55") (name "Net-(D6-C1A2)") (class "Default")
      (node (ref "D6") (pin "3") (pinfunction "C1A2_3") (pintype "passive"))
      (node (ref "R58") (pin "1") (pinfunction "1_1") (pintype "passive"))
      (node (ref "R6") (pin "2") (pinfunction "2_2") (pintype "passive"))
      (node (ref "R9") (pin "2") (pinfunction "2_2") (pintype "passive"))
    )
    (net (code "56") (name "Net-(D7-C1A2)") (class "Default")
      (node (ref "D7") (pin "3") (pinfunction "C1A2_3") (pintype "passive"))
      (node (ref "R20") (pin "2") (pinfunction "2_2") (pintype "passive"))
      (node (ref "R21") (pin "2") (pinfunction "2_2") (pintype "passive"))
      (node (ref "R22") (pin "1") (pinfunction "1_1") (pintype "passive"))
    )
    (net (code "57") (name "Net-(D8-C1A2)") (class "Default")
      (node (ref "D8") (pin "3") (pinfunction "C1A2_3") (pintype "passive"))
      (node (ref "R23") (pin "2") (pinfunction "2_2") (pintype "passive"))
      (node (ref "R26") (pin "2") (pinfunction "2_2") (pintype "passive"))
      (node (ref "R28") (pin "1") (pinfunction "1_1") (pintype "passive"))
    )
    (net (code "58") (name "Net-(D9-C1A2)") (class "Default")
      (node (ref "D9") (pin "3") (pinfunction "C1A2_3") (pintype "passive"))
      (node (ref "R29") (pin "2") (pinfunction "2_2") (pintype "passive"))
      (node (ref "R30") (pin "2") (pinfunction "2_2") (pintype "passive"))
      (node (ref "R31") (pin "1") (pinfunction "1_1") (pintype "passive"))
    )
    (net (code "59") (name "Net-(D10-C1A2)") (class "Default")
      (node (ref "D10") (pin "3") (pinfunction "C1A2_3") (pintype "passive"))
      (node (ref "R32") (pin "2") (pinfunction "2_2") (pintype "passive"))
      (node (ref "R33") (pin "2") (pinfunction "2_2") (pintype "passive"))
      (node (ref "R34") (pin "1") (pinfunction "1_1") (pintype "passive"))
    )
    (net (code "60") (name "Net-(D11-C1A2)") (class "Default")
      (node (ref "D11") (pin "3") (pinfunction "C1A2_3") (pintype "passive"))
      (node (ref "R37") (pin "2") (pinfunction "2_2") (pintype "passive"))
      (node (ref "R38") (pin "2") (pinfunction "2_2") (pintype "passive"))
      (node (ref "R39") (pin "1") (pinfunction "1_1") (pintype "passive"))
    )
    (net (code "61") (name "Net-(D12-C1A2)") (class "Default")
      (node (ref "D12") (pin "3") (pinfunction "C1A2_3") (pintype "passive"))
      (node (ref "R40") (pin "2") (pinfunction "2_2") (pintype "passive"))
      (node (ref "R41") (pin "2") (pinfunction "2_2") (pintype "passive"))
      (node (ref "R42") (pin "1") (pinfunction "1_1") (pintype "passive"))
    )
    (net (code "62") (name "Net-(D13-C1A2)") (class "Default")
      (node (ref "D13") (pin "3") (pinfunction "C1A2_3") (pintype "passive"))
      (node (ref "R43") (pin "2") (pinfunction "2_2") (pintype "passive"))
      (node (ref "R44") (pin "2") (pinfunction "2_2") (pintype "passive"))
      (node (ref "R45") (pin "1") (pinfunction "1_1") (pintype "passive"))
    )
    (net (code "63") (name "Net-(D14-C1A2)") (class "Default")
      (node (ref "D14") (pin "3") (pinfunction "C1A2_3") (pintype "passive"))
      (node (ref "R46") (pin "2") (pinfunction "2_2") (pintype "passive"))
      (node (ref "R47") (pin "2") (pinfunction "2_2") (pintype "passive"))
      (node (ref "R48") (pin "1") (pinfunction "1_1") (pintype "passive"))
    )
    (net (code "64") (name "Net-(D15-C1A2)") (class "Default")
      (node (ref "D15") (pin "3") (pinfunction "C1A2_3") (pintype "passive"))
      (node (ref "R49") (pin "2") (pinfunction "2_2") (pintype "passive"))
      (node (ref "R50") (pin "2") (pinfunction "2_2") (pintype "passive"))
      (node (ref "R51") (pin "1") (pinfunction "1_1") (pintype "passive"))
    )
    (net (code "65") (name "Net-(D16-C1A2)") (class "Default")
      (node (ref "D16") (pin "3") (pinfunction "C1A2_3") (pintype "passive"))
      (node (ref "R52") (pin "2") (pinfunction "2_2") (pintype "passive"))
      (node (ref "R53") (pin "2") (pinfunction "2_2") (pintype "passive"))
      (node (ref "R54") (pin "1") (pinfunction "1_1") (pintype "passive"))
    )
    (net (code "66") (name "Net-(D17-C1A2)") (class "Default")
      (node (ref "D17") (pin "3") (pinfunction "C1A2_3") (pintype "passive"))
      (node (ref "R55") (pin "2") (pinfunction "2_2") (pintype "passive"))
      (node (ref "R56") (pin "2") (pinfunction "2_2") (pintype "passive"))
      (node (ref "R57") (pin "1") (pinfunction "1_1") (pintype "passive"))
    )
    (net (code "67") (name "Net-(D18-C1A2)") (class "Default")
      (node (ref "D18") (pin "3") (pinfunction "C1A2_3") (pintype "passive"))
      (node (ref "R61") (pin "1") (pinfunction "1_1") (pintype "passive"))
      (node (ref "R62") (pin "2") (pinfunction "2_2") (pintype "passive"))
    )
    (net (code "68") (name "Net-(DA1-RS)") (class "Default")
      (node (ref "DA1") (pin "8") (pinfunction "RS_8") (pintype "bidirectional"))
      (node (ref "R24") (pin "1") (pinfunction "1_1") (pintype "passive"))
    )
    (net (code "69") (name "Net-(F1-Pad2)") (class "Default")
      (node (ref "F1") (pin "2") (pinfunction "2_2") (pintype "passive"))
      (node (ref "U$4") (pin "OUT") (pinfunction "OUT_OUT") (pintype "bidirectional"))
    )
    (net (code "70") (name "Net-(JP2-Pad2)") (class "Default")
      (node (ref "JP2") (pin "2") (pinfunction "2_2") (pintype "passive"))
      (node (ref "R2") (pin "1") (pinfunction "1_1") (pintype "passive"))
    )
    (net (code "71") (name "Net-(LED1-PadC)") (class "Default")
      (node (ref "LED1") (pin "C") (pinfunction "C_C") (pintype "passive"))
      (node (ref "R5") (pin "2") (pinfunction "2_2") (pintype "passive"))
    )
    (net (code "72") (name "Net-(LED2-PadC)") (class "Default")
      (node (ref "LED2") (pin "C") (pinfunction "C_C") (pintype "passive"))
      (node (ref "R4") (pin "2") (pinfunction "2_2") (pintype "passive"))
    )
    (net (code "73") (name "Net-(R1-Pad2)") (class "Default")
      (node (ref "R1") (pin "2") (pinfunction "2_2") (pintype "passive"))
      (node (ref "S1") (pin "3") (pinfunction "3_3") (pintype "passive"))
      (node (ref "S1") (pin "4") (pinfunction "4_4") (pintype "passive"))
      (node (ref "U$1") (pin "NRST") (pinfunction "NRST_NRST") (pintype "bidirectional"))
    )
    (net (code "74") (name "Net-(R63-Pad1)") (class "Default")
      (node (ref "R63") (pin "1") (pinfunction "1_1") (pintype "passive"))
      (node (ref "SJ1") (pin "3") (pinfunction "3_3") (pintype "passive"))
    )
    (net (code "75") (name "Net-(R64-Pad1)") (class "Default")
      (node (ref "R64") (pin "1") (pinfunction "1_1") (pintype "passive"))
      (node (ref "SJ1") (pin "1") (pinfunction "1_1") (pintype "passive"))
    )
    (net (code "76") (name "Net-(R65-Pad1)") (class "Default")
      (node (ref "R65") (pin "1") (pinfunction "1_1") (pintype "passive"))
      (node (ref "SJ2") (pin "3") (pinfunction "3_3") (pintype "passive"))
    )
    (net (code "77") (name "Net-(R66-Pad1)") (class "Default")
      (node (ref "R66") (pin "1") (pinfunction "1_1") (pintype "passive"))
      (node (ref "SJ2") (pin "1") (pinfunction "1_1") (pintype "passive"))
    )
    (net (code "78") (name "PRE_FUSE_12V") (class "Default")
      (node (ref "F2") (pin "1") (pinfunction "1_1") (pintype "passive"))
      (node (ref "GND8") (pin "1") (pinfunction "1_1") (pintype "passive"))
      (node (ref "X1") (pin "4") (pinfunction "4_4") (pintype "passive"))
      (node (ref "X1") (pin "5") (pinfunction "5_5") (pintype "passive"))
      (node (ref "X1") (pin "6") (pinfunction "6_6") (pintype "passive"))
      (node (ref "X2") (pin "4") (pinfunction "4_4") (pintype "passive"))
      (node (ref "X2") (pin "5") (pinfunction "5_5") (pintype "passive"))
      (node (ref "X2") (pin "6") (pinfunction "6_6") (pintype "passive"))
    )
    (net (code "79") (name "SWCLK") (class "Default")
      (node (ref "PROGRAMMER") (pin "1") (pinfunction "1_1") (pintype "passive"))
      (node (ref "U$1") (pin "PA14") (pinfunction "PA14_PA14") (pintype "bidirectional"))
    )
    (net (code "80") (name "SWDIO") (class "Default")
      (node (ref "PROGRAMMER") (pin "3") (pinfunction "3_3") (pintype "passive"))
      (node (ref "U$1") (pin "PA13") (pinfunction "PA13_PA13") (pintype "bidirectional"))
    )
    (net (code "81") (name "TAMPER") (class "Default")
      (node (ref "R61") (pin "2") (pinfunction "2_2") (pintype "passive"))
      (node (ref "U$1") (pin "PB12") (pinfunction "PB12_PB12") (pintype "bidirectional"))
    )
    (net (code "82") (name "UART_RX") (class "Default")
      (node (ref "J1") (pin "1") (pinfunction "1_1") (pintype "passive"))
      (node (ref "U$1") (pin "PA10") (pinfunction "PA10_PA10") (pintype "bidirectional"))
    )
    (net (code "83") (name "UART_TX") (class "Default")
      (node (ref "J1") (pin "2") (pinfunction "2_2") (pintype "passive"))
      (node (ref "U$1") (pin "PA9") (pinfunction "PA9_PA9") (pintype "bidirectional"))
    )
    (net (code "84") (name "unconnected-(DA1-VREF-Pad5)") (class "Default")
      (node (ref "DA1") (pin "5") (pinfunction "VREF_5") (pintype "bidirectional"))
    )
    (net (code "85") (name "unconnected-(U$1-PadPA8)") (class "Default")
      (node (ref "U$1") (pin "PA8") (pinfunction "PA8_PA8") (pintype "bidirectional"))
    )
    (net (code "86") (name "unconnected-(U$1-PadPA15)") (class "Default")
      (node (ref "U$1") (pin "PA15") (pinfunction "PA15_PA15") (pintype "bidirectional"))
    )
    (net (code "87") (name "unconnected-(U$1-PadPB3)") (class "Default")
      (node (ref "U$1") (pin "PB3") (pinfunction "PB3_PB3") (pintype "bidirectional"))
    )
    (net (code "88") (name "unconnected-(U$1-PadPB4)") (class "Default")
      (node (ref "U$1") (pin "PB4") (pinfunction "PB4_PB4") (pintype "bidirectional"))
    )
    (net (code "89") (name "unconnected-(U$1-PadPB5)") (class "Default")
      (node (ref "U$1") (pin "PB5") (pinfunction "PB5_PB5") (pintype "bidirectional"))
    )
    (net (code "90") (name "unconnected-(U$1-PadPB8)") (class "Default")
      (node (ref "U$1") (pin "PB8") (pinfunction "PB8_PB8") (pintype "bidirectional"))
    )
    (net (code "91") (name "unconnected-(U$1-PadPB9)") (class "Default")
      (node (ref "U$1") (pin "PB9") (pinfunction "PB9_PB9") (pintype "bidirectional"))
    )
    (net (code "92") (name "unconnected-(U$1-PadPB10)") (class "Default")
      (node (ref "U$1") (pin "PB10") (pinfunction "PB10_PB10") (pintype "bidirectional"))
    )
    (net (code "93") (name "unconnected-(U$1-PadPB11)") (class "Default")
      (node (ref "U$1") (pin "PB11") (pinfunction "PB11_PB11") (pintype "bidirectional"))
    )
    (net (code "94") (name "unconnected-(U$1-PadPB13)") (class "Default")
      (node (ref "U$1") (pin "PB13") (pinfunction "PB13_PB13") (pintype "bidirectional"))
    )
    (net (code "95") (name "unconnected-(U$1-PadPB14)") (class "Default")
      (node (ref "U$1") (pin "PB14") (pinfunction "PB14_PB14") (pintype "bidirectional"))
    )
    (net (code "96") (name "unconnected-(U$1-PadPB15)") (class "Default")
      (node (ref "U$1") (pin "PB15") (pinfunction "PB15_PB15") (pintype "bidirectional"))
    )
    (net (code "97") (name "unconnected-(U$1-PadPC6)") (class "Default")
      (node (ref "U$1") (pin "PC6") (pinfunction "PC6_PC6") (pintype "bidirectional"))
    )
    (net (code "98") (name "unconnected-(U$1-PadPC7)") (class "Default")
      (node (ref "U$1") (pin "PC7") (pinfunction "PC7_PC7") (pintype "bidirectional"))
    )
    (net (code "99") (name "unconnected-(U$1-PadPC8)") (class "Default")
      (node (ref "U$1") (pin "PC8") (pinfunction "PC8_PC8") (pintype "bidirectional"))
    )
    (net (code "100") (name "unconnected-(U$1-PadPC9)") (class "Default")
      (node (ref "U$1") (pin "PC9") (pinfunction "PC9_PC9") (pintype "bidirectional"))
    )
    (net (code "101") (name "unconnected-(U$1-PadPC10)") (class "Default")
      (node (ref "U$1") (pin "PC10") (pinfunction "PC10_PC10") (pintype "bidirectional"))
    )
    (net (code "102") (name "unconnected-(U$1-PadPC11)") (class "Default")
      (node (ref "U$1") (pin "PC11") (pinfunction "PC11_PC11") (pintype "bidirectional"))
    )
    (net (code "103") (name "unconnected-(U$1-PadPC12)") (class "Default")
      (node (ref "U$1") (pin "PC12") (pinfunction "PC12_PC12") (pintype "bidirectional"))
    )
    (net (code "104") (name "unconnected-(U$1-PadPC14)") (class "Default")
      (node (ref "U$1") (pin "PC14") (pinfunction "PC14_PC14") (pintype "bidirectional"))
    )
    (net (code "105") (name "unconnected-(U$1-PadPC15)") (class "Default")
      (node (ref "U$1") (pin "PC15") (pinfunction "PC15_PC15") (pintype "bidirectional"))
    )
    (net (code "106") (name "unconnected-(U$1-PadPD0)") (class "Default")
      (node (ref "U$1") (pin "PD0") (pinfunction "PD0_PD0") (pintype "bidirectional"))
    )
    (net (code "107") (name "unconnected-(U$1-PadPD1)") (class "Default")
      (node (ref "U$1") (pin "PD1") (pinfunction "PD1_PD1") (pintype "bidirectional"))
    )
    (net (code "108") (name "unconnected-(U$1-PadPD2)") (class "Default")
      (node (ref "U$1") (pin "PD2") (pinfunction "PD2_PD2") (pintype "bidirectional"))
    )
    (net (code "109") (name "unconnected-(U$1-PadPD3)") (class "Default")
      (node (ref "U$1") (pin "PD3") (pinfunction "PD3_PD3") (pintype "bidirectional"))
    )
    (net (code "110") (name "unconnected-(U$1-PadPD4)") (class "Default")
      (node (ref "U$1") (pin "PD4") (pinfunction "PD4_PD4") (pintype "bidirectional"))
    )
    (net (code "111") (name "unconnected-(U$1-PadPD5)") (class "Default")
      (node (ref "U$1") (pin "PD5") (pinfunction "PD5_PD5") (pintype "bidirectional"))
    )
    (net (code "112") (name "unconnected-(U$1-PadPD6)") (class "Default")
      (node (ref "U$1") (pin "PD6") (pinfunction "PD6_PD6") (pintype "bidirectional"))
    )
    (net (code "113") (name "unconnected-(U$1-PadPD7)") (class "Default")
      (node (ref "U$1") (pin "PD7") (pinfunction "PD7_PD7") (pintype "bidirectional"))
    )
    (net (code "114") (name "unconnected-(U$1-PadPD8)") (class "Default")
      (node (ref "U$1") (pin "PD8") (pinfunction "PD8_PD8") (pintype "bidirectional"))
    )
    (net (code "115") (name "unconnected-(U$1-PadPD9)") (class "Default")
      (node (ref "U$1") (pin "PD9") (pinfunction "PD9_PD9") (pintype "bidirectional"))
    )
    (net (code "116") (name "unconnected-(U$1-PadPD10)") (class "Default")
      (node (ref "U$1") (pin "PD10") (pinfunction "PD10_PD10") (pintype "bidirectional"))
    )
    (net (code "117") (name "unconnected-(U$1-PadPD11)") (class "Default")
      (node (ref "U$1") (pin "PD11") (pinfunction "PD11_PD11") (pintype "bidirectional"))
    )
    (net (code "118") (name "unconnected-(U$1-PadPD12)") (class "Default")
      (node (ref "U$1") (pin "PD12") (pinfunction "PD12_PD12") (pintype "bidirectional"))
    )
    (net (code "119") (name "unconnected-(U$1-PadPD13)") (class "Default")
      (node (ref "U$1") (pin "PD13") (pinfunction "PD13_PD13") (pintype "bidirectional"))
    )
    (net (code "120") (name "unconnected-(U$1-PadPD14)") (class "Default")
      (node (ref "U$1") (pin "PD14") (pinfunction "PD14_PD14") (pintype "bidirectional"))
    )
    (net (code "121") (name "unconnected-(U$1-PadPD15)") (class "Default")
      (node (ref "U$1") (pin "PD15") (pinfunction "PD15_PD15") (pintype "bidirectional"))
    )
    (net (code "122") (name "unconnected-(U$1-PadPE1)") (class "Default")
      (node (ref "U$1") (pin "PE1") (pinfunction "PE1_PE1") (pintype "bidirectional"))
    )
    (net (code "123") (name "unconnected-(U$1-PadPE2)") (class "Default")
      (node (ref "U$1") (pin "PE2") (pinfunction "PE2_PE2") (pintype "bidirectional"))
    )
    (net (code "124") (name "unconnected-(U$1-PadPE3)") (class "Default")
      (node (ref "U$1") (pin "PE3") (pinfunction "PE3_PE3") (pintype "bidirectional"))
    )
    (net (code "125") (name "unconnected-(U$1-PadPE4)") (class "Default")
      (node (ref "U$1") (pin "PE4") (pinfunction "PE4_PE4") (pintype "bidirectional"))
    )
    (net (code "126") (name "unconnected-(U$1-PadPE5)") (class "Default")
      (node (ref "U$1") (pin "PE5") (pinfunction "PE5_PE5") (pintype "bidirectional"))
    )
    (net (code "127") (name "unconnected-(U$1-PadPE6)") (class "Default")
      (node (ref "U$1") (pin "PE6") (pinfunction "PE6_PE6") (pintype "bidirectional"))
    )
    (net (code "128") (name "unconnected-(U$1-PadPE7)") (class "Default")
      (node (ref "U$1") (pin "PE7") (pinfunction "PE7_PE7") (pintype "bidirectional"))
    )
    (net (code "129") (name "unconnected-(U$1-PadPE8)") (class "Default")
      (node (ref "U$1") (pin "PE8") (pinfunction "PE8_PE8") (pintype "bidirectional"))
    )
    (net (code "130") (name "unconnected-(U$1-PadPE9)") (class "Default")
      (node (ref "U$1") (pin "PE9") (pinfunction "PE9_PE9") (pintype "bidirectional"))
    )
    (net (code "131") (name "unconnected-(U$1-PadPE10)") (class "Default")
      (node (ref "U$1") (pin "PE10") (pinfunction "PE10_PE10") (pintype "bidirectional"))
    )
    (net (code "132") (name "unconnected-(U$1-PadPE11)") (class "Default")
      (node (ref "U$1") (pin "PE11") (pinfunction "PE11_PE11") (pintype "bidirectional"))
    )
    (net (code "133") (name "unconnected-(U$1-PadPE12)") (class "Default")
      (node (ref "U$1") (pin "PE12") (pinfunction "PE12_PE12") (pintype "bidirectional"))
    )
    (net (code "134") (name "unconnected-(U$1-PadPE13)") (class "Default")
      (node (ref "U$1") (pin "PE13") (pinfunction "PE13_PE13") (pintype "bidirectional"))
    )
    (net (code "135") (name "unconnected-(U$1-PadPE14)") (class "Default")
      (node (ref "U$1") (pin "PE14") (pinfunction "PE14_PE14") (pintype "bidirectional"))
    )
    (net (code "136") (name "unconnected-(U$1-PadPE15)") (class "Default")
      (node (ref "U$1") (pin "PE15") (pinfunction "PE15_PE15") (pintype "bidirectional"))
    )
    (net (code "137") (name "unconnected-(U$1-PadVBAT)") (class "Default")
      (node (ref "U$1") (pin "VBAT") (pinfunction "VBAT_VBAT") (pintype "bidirectional"))
    )
    (net (code "138") (name "unconnected-(U$4-PadEN)") (class "Default")
      (node (ref "U$4") (pin "EN") (pinfunction "EN_EN") (pintype "bidirectional"))
    )
  )
)
